# mehhhh.net
KiCad netlist of a schematic drawn in EAGLE
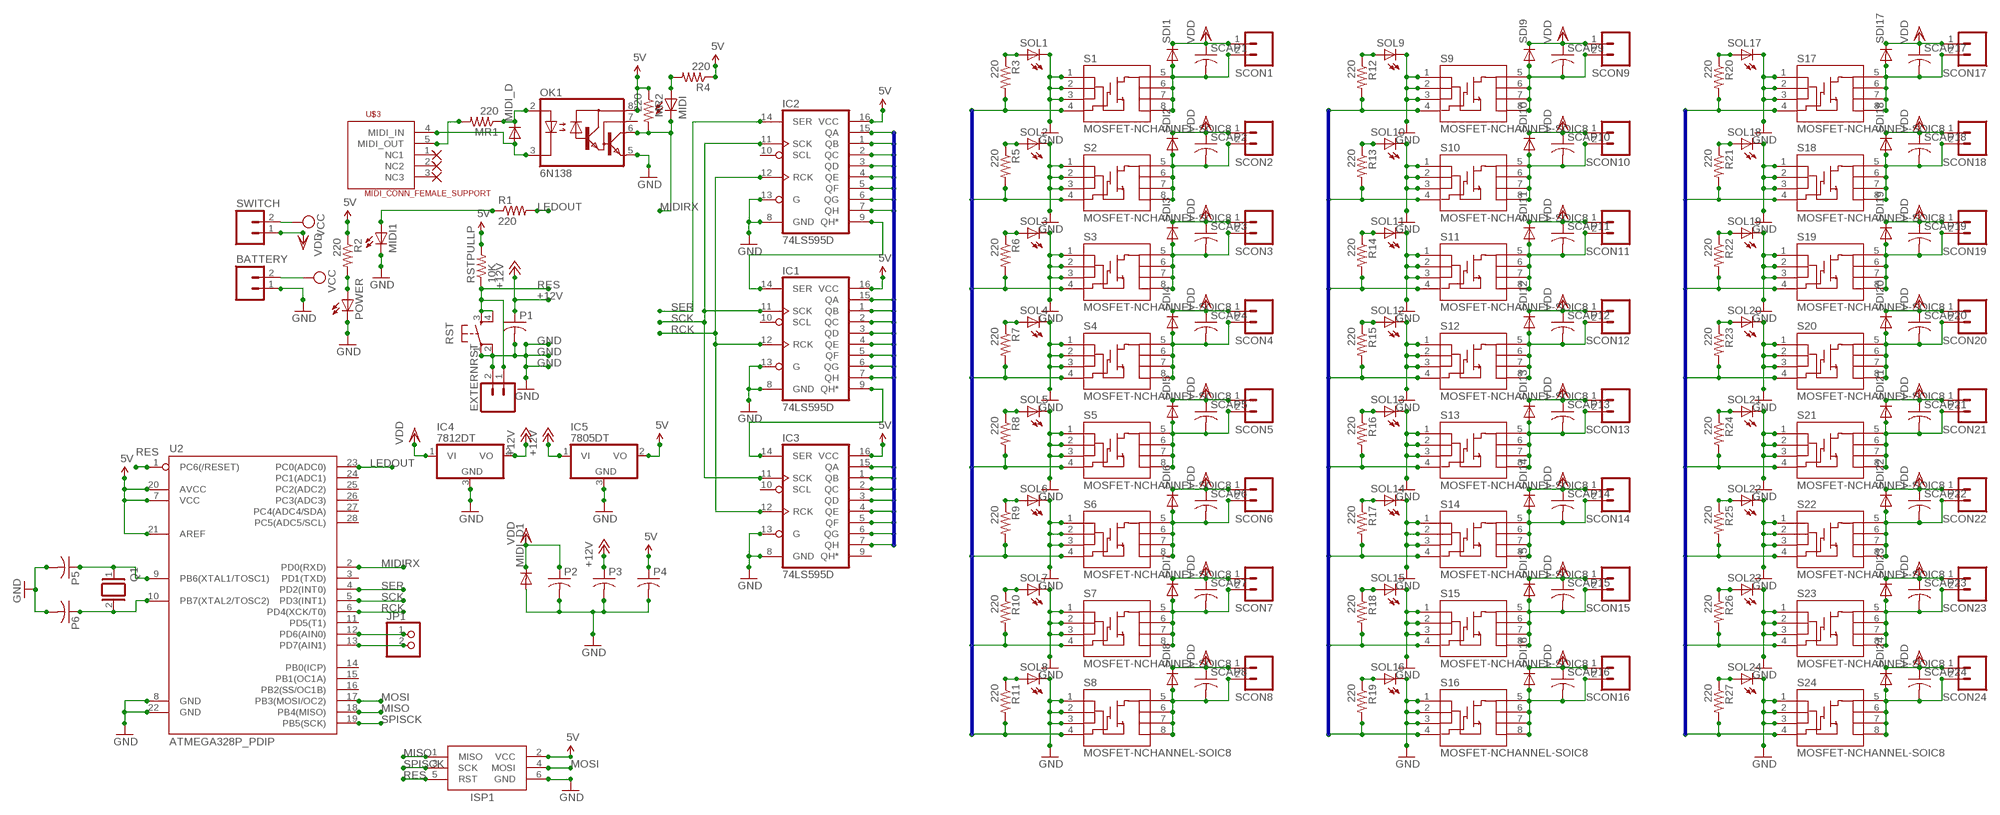
[diagram p0: schematic, sheet 1]

(export (version "E")
  (design (tool "Eeschema 10.0.6"))
  (components
    (comp (ref "BATTERY")
      (value "M023.5MM")
      (footprint "eagle-import:SCREWTERMINAL-3.5MM-2")
      (libsource (lib "eagle-import") (part "M023.5MM"))
    )
    (comp (ref "EXTERNRST")
      (value "M023.5MM")
      (footprint "eagle-import:SCREWTERMINAL-3.5MM-2")
      (libsource (lib "eagle-import") (part "M023.5MM"))
    )
    (comp (ref "IC1")
      (value "74LS595D")
      (footprint "eagle-import:SO16")
      (libsource (lib "eagle-import") (part "74595DLS"))
    )
    (comp (ref "IC2")
      (value "74LS595D")
      (footprint "eagle-import:SO16")
      (libsource (lib "eagle-import") (part "74595DLS"))
    )
    (comp (ref "IC3")
      (value "74LS595D")
      (footprint "eagle-import:SO16")
      (libsource (lib "eagle-import") (part "74595DLS"))
    )
    (comp (ref "IC4")
      (value "7812DT")
      (footprint "eagle-import:TO252")
      (libsource (lib "eagle-import") (part "78DT12"))
    )
    (comp (ref "IC5")
      (value "7805DT")
      (footprint "eagle-import:TO252")
      (libsource (lib "eagle-import") (part "78DT05"))
    )
    (comp (ref "ISP1")
      (value "AVRISP-6")
      (footprint "eagle-import:AVRISP")
      (libsource (lib "eagle-import") (part "AVRISP-6"))
    )
    (comp (ref "JP1")
      (value "PINHD-1X2")
      (footprint "eagle-import:1X02")
      (libsource (lib "eagle-import") (part "PINHD-1X2"))
    )
    (comp (ref "MIDI")
      (value "LEDCHIPLED_1206")
      (footprint "eagle-import:CHIPLED_1206")
      (libsource (lib "eagle-import") (part "LEDCHIPLED_1206"))
    )
    (comp (ref "MIDI1")
      (value "LEDCHIPLED_1206")
      (footprint "eagle-import:CHIPLED_1206")
      (libsource (lib "eagle-import") (part "LEDCHIPLED_1206"))
    )
    (comp (ref "MIDI_D")
      (value "DIODESMA-ALT")
      (footprint "eagle-import:SMA-DIODE_ALT")
      (libsource (lib "eagle-import") (part "DIODESMA-ALT"))
    )
    (comp (ref "MIDI_D1")
      (value "DIODESMA-ALT")
      (footprint "eagle-import:SMA-DIODE_ALT")
      (libsource (lib "eagle-import") (part "DIODESMA-ALT"))
    )
    (comp (ref "MR1")
      (value "220")
      (footprint "eagle-import:1206")
      (libsource (lib "eagle-import") (part "RESISTOR1206"))
    )
    (comp (ref "MR2")
      (value "220")
      (footprint "eagle-import:1206")
      (libsource (lib "eagle-import") (part "RESISTOR1206"))
    )
    (comp (ref "OK1")
      (value "6N138")
      (footprint "eagle-import:DIL08")
      (libsource (lib "eagle-import") (part "6N138"))
    )
    (comp (ref "P1")
      (value "C-USC1206")
      (footprint "eagle-import:C1206")
      (libsource (lib "eagle-import") (part "C-USC1206"))
    )
    (comp (ref "P2")
      (value "C-USC1206")
      (footprint "eagle-import:C1206")
      (libsource (lib "eagle-import") (part "C-USC1206"))
    )
    (comp (ref "P3")
      (value "C-USC1206")
      (footprint "eagle-import:C1206")
      (libsource (lib "eagle-import") (part "C-USC1206"))
    )
    (comp (ref "P4")
      (value "C-USC1206")
      (footprint "eagle-import:C1206")
      (libsource (lib "eagle-import") (part "C-USC1206"))
    )
    (comp (ref "P5")
      (value "C-USC1206")
      (footprint "eagle-import:C1206")
      (libsource (lib "eagle-import") (part "C-USC1206"))
    )
    (comp (ref "P6")
      (value "C-USC1206")
      (footprint "eagle-import:C1206")
      (libsource (lib "eagle-import") (part "C-USC1206"))
    )
    (comp (ref "POWER")
      (value "LEDCHIPLED_1206")
      (footprint "eagle-import:CHIPLED_1206")
      (libsource (lib "eagle-import") (part "LEDCHIPLED_1206"))
    )
    (comp (ref "Q1")
      (value "XTAL/S")
      (footprint "eagle-import:QS")
      (libsource (lib "eagle-import") (part "XTAL/S"))
    )
    (comp (ref "R1")
      (value "220")
      (footprint "eagle-import:1206")
      (libsource (lib "eagle-import") (part "RESISTOR1206"))
    )
    (comp (ref "R2")
      (value "220")
      (footprint "eagle-import:1206")
      (libsource (lib "eagle-import") (part "RESISTOR1206"))
    )
    (comp (ref "R3")
      (value "220")
      (footprint "eagle-import:1206")
      (libsource (lib "eagle-import") (part "RESISTOR1206"))
    )
    (comp (ref "R4")
      (value "220")
      (footprint "eagle-import:1206")
      (libsource (lib "eagle-import") (part "RESISTOR1206"))
    )
    (comp (ref "R5")
      (value "220")
      (footprint "eagle-import:1206")
      (libsource (lib "eagle-import") (part "RESISTOR1206"))
    )
    (comp (ref "R6")
      (value "220")
      (footprint "eagle-import:1206")
      (libsource (lib "eagle-import") (part "RESISTOR1206"))
    )
    (comp (ref "R7")
      (value "220")
      (footprint "eagle-import:1206")
      (libsource (lib "eagle-import") (part "RESISTOR1206"))
    )
    (comp (ref "R8")
      (value "220")
      (footprint "eagle-import:1206")
      (libsource (lib "eagle-import") (part "RESISTOR1206"))
    )
    (comp (ref "R9")
      (value "220")
      (footprint "eagle-import:1206")
      (libsource (lib "eagle-import") (part "RESISTOR1206"))
    )
    (comp (ref "R10")
      (value "220")
      (footprint "eagle-import:1206")
      (libsource (lib "eagle-import") (part "RESISTOR1206"))
    )
    (comp (ref "R11")
      (value "220")
      (footprint "eagle-import:1206")
      (libsource (lib "eagle-import") (part "RESISTOR1206"))
    )
    (comp (ref "R12")
      (value "220")
      (footprint "eagle-import:1206")
      (libsource (lib "eagle-import") (part "RESISTOR1206"))
    )
    (comp (ref "R13")
      (value "220")
      (footprint "eagle-import:1206")
      (libsource (lib "eagle-import") (part "RESISTOR1206"))
    )
    (comp (ref "R14")
      (value "220")
      (footprint "eagle-import:1206")
      (libsource (lib "eagle-import") (part "RESISTOR1206"))
    )
    (comp (ref "R15")
      (value "220")
      (footprint "eagle-import:1206")
      (libsource (lib "eagle-import") (part "RESISTOR1206"))
    )
    (comp (ref "R16")
      (value "220")
      (footprint "eagle-import:1206")
      (libsource (lib "eagle-import") (part "RESISTOR1206"))
    )
    (comp (ref "R17")
      (value "220")
      (footprint "eagle-import:1206")
      (libsource (lib "eagle-import") (part "RESISTOR1206"))
    )
    (comp (ref "R18")
      (value "220")
      (footprint "eagle-import:1206")
      (libsource (lib "eagle-import") (part "RESISTOR1206"))
    )
    (comp (ref "R19")
      (value "220")
      (footprint "eagle-import:1206")
      (libsource (lib "eagle-import") (part "RESISTOR1206"))
    )
    (comp (ref "R20")
      (value "220")
      (footprint "eagle-import:1206")
      (libsource (lib "eagle-import") (part "RESISTOR1206"))
    )
    (comp (ref "R21")
      (value "220")
      (footprint "eagle-import:1206")
      (libsource (lib "eagle-import") (part "RESISTOR1206"))
    )
    (comp (ref "R22")
      (value "220")
      (footprint "eagle-import:1206")
      (libsource (lib "eagle-import") (part "RESISTOR1206"))
    )
    (comp (ref "R23")
      (value "220")
      (footprint "eagle-import:1206")
      (libsource (lib "eagle-import") (part "RESISTOR1206"))
    )
    (comp (ref "R24")
      (value "220")
      (footprint "eagle-import:1206")
      (libsource (lib "eagle-import") (part "RESISTOR1206"))
    )
    (comp (ref "R25")
      (value "220")
      (footprint "eagle-import:1206")
      (libsource (lib "eagle-import") (part "RESISTOR1206"))
    )
    (comp (ref "R26")
      (value "220")
      (footprint "eagle-import:1206")
      (libsource (lib "eagle-import") (part "RESISTOR1206"))
    )
    (comp (ref "R27")
      (value "220")
      (footprint "eagle-import:1206")
      (libsource (lib "eagle-import") (part "RESISTOR1206"))
    )
    (comp (ref "RST")
      (value "TAC_SWITCHPTH")
      (footprint "eagle-import:TACTILE-PTH")
      (libsource (lib "eagle-import") (part "TAC_SWITCHPTH"))
    )
    (comp (ref "RSTPULLP")
      (value "10K")
      (footprint "eagle-import:1206")
      (libsource (lib "eagle-import") (part "RESISTOR1206"))
    )
    (comp (ref "S1")
      (value "MOSFET-NCHANNEL-SOIC8")
      (footprint "eagle-import:SO08")
      (libsource (lib "eagle-import") (part "MOSFET-NCHANNEL-SOIC8"))
    )
    (comp (ref "S2")
      (value "MOSFET-NCHANNEL-SOIC8")
      (footprint "eagle-import:SO08")
      (libsource (lib "eagle-import") (part "MOSFET-NCHANNEL-SOIC8"))
    )
    (comp (ref "S3")
      (value "MOSFET-NCHANNEL-SOIC8")
      (footprint "eagle-import:SO08")
      (libsource (lib "eagle-import") (part "MOSFET-NCHANNEL-SOIC8"))
    )
    (comp (ref "S4")
      (value "MOSFET-NCHANNEL-SOIC8")
      (footprint "eagle-import:SO08")
      (libsource (lib "eagle-import") (part "MOSFET-NCHANNEL-SOIC8"))
    )
    (comp (ref "S5")
      (value "MOSFET-NCHANNEL-SOIC8")
      (footprint "eagle-import:SO08")
      (libsource (lib "eagle-import") (part "MOSFET-NCHANNEL-SOIC8"))
    )
    (comp (ref "S6")
      (value "MOSFET-NCHANNEL-SOIC8")
      (footprint "eagle-import:SO08")
      (libsource (lib "eagle-import") (part "MOSFET-NCHANNEL-SOIC8"))
    )
    (comp (ref "S7")
      (value "MOSFET-NCHANNEL-SOIC8")
      (footprint "eagle-import:SO08")
      (libsource (lib "eagle-import") (part "MOSFET-NCHANNEL-SOIC8"))
    )
    (comp (ref "S8")
      (value "MOSFET-NCHANNEL-SOIC8")
      (footprint "eagle-import:SO08")
      (libsource (lib "eagle-import") (part "MOSFET-NCHANNEL-SOIC8"))
    )
    (comp (ref "S9")
      (value "MOSFET-NCHANNEL-SOIC8")
      (footprint "eagle-import:SO08")
      (libsource (lib "eagle-import") (part "MOSFET-NCHANNEL-SOIC8"))
    )
    (comp (ref "S10")
      (value "MOSFET-NCHANNEL-SOIC8")
      (footprint "eagle-import:SO08")
      (libsource (lib "eagle-import") (part "MOSFET-NCHANNEL-SOIC8"))
    )
    (comp (ref "S11")
      (value "MOSFET-NCHANNEL-SOIC8")
      (footprint "eagle-import:SO08")
      (libsource (lib "eagle-import") (part "MOSFET-NCHANNEL-SOIC8"))
    )
    (comp (ref "S12")
      (value "MOSFET-NCHANNEL-SOIC8")
      (footprint "eagle-import:SO08")
      (libsource (lib "eagle-import") (part "MOSFET-NCHANNEL-SOIC8"))
    )
    (comp (ref "S13")
      (value "MOSFET-NCHANNEL-SOIC8")
      (footprint "eagle-import:SO08")
      (libsource (lib "eagle-import") (part "MOSFET-NCHANNEL-SOIC8"))
    )
    (comp (ref "S14")
      (value "MOSFET-NCHANNEL-SOIC8")
      (footprint "eagle-import:SO08")
      (libsource (lib "eagle-import") (part "MOSFET-NCHANNEL-SOIC8"))
    )
    (comp (ref "S15")
      (value "MOSFET-NCHANNEL-SOIC8")
      (footprint "eagle-import:SO08")
      (libsource (lib "eagle-import") (part "MOSFET-NCHANNEL-SOIC8"))
    )
    (comp (ref "S16")
      (value "MOSFET-NCHANNEL-SOIC8")
      (footprint "eagle-import:SO08")
      (libsource (lib "eagle-import") (part "MOSFET-NCHANNEL-SOIC8"))
    )
    (comp (ref "S17")
      (value "MOSFET-NCHANNEL-SOIC8")
      (footprint "eagle-import:SO08")
      (libsource (lib "eagle-import") (part "MOSFET-NCHANNEL-SOIC8"))
    )
    (comp (ref "S18")
      (value "MOSFET-NCHANNEL-SOIC8")
      (footprint "eagle-import:SO08")
      (libsource (lib "eagle-import") (part "MOSFET-NCHANNEL-SOIC8"))
    )
    (comp (ref "S19")
      (value "MOSFET-NCHANNEL-SOIC8")
      (footprint "eagle-import:SO08")
      (libsource (lib "eagle-import") (part "MOSFET-NCHANNEL-SOIC8"))
    )
    (comp (ref "S20")
      (value "MOSFET-NCHANNEL-SOIC8")
      (footprint "eagle-import:SO08")
      (libsource (lib "eagle-import") (part "MOSFET-NCHANNEL-SOIC8"))
    )
    (comp (ref "S21")
      (value "MOSFET-NCHANNEL-SOIC8")
      (footprint "eagle-import:SO08")
      (libsource (lib "eagle-import") (part "MOSFET-NCHANNEL-SOIC8"))
    )
    (comp (ref "S22")
      (value "MOSFET-NCHANNEL-SOIC8")
      (footprint "eagle-import:SO08")
      (libsource (lib "eagle-import") (part "MOSFET-NCHANNEL-SOIC8"))
    )
    (comp (ref "S23")
      (value "MOSFET-NCHANNEL-SOIC8")
      (footprint "eagle-import:SO08")
      (libsource (lib "eagle-import") (part "MOSFET-NCHANNEL-SOIC8"))
    )
    (comp (ref "S24")
      (value "MOSFET-NCHANNEL-SOIC8")
      (footprint "eagle-import:SO08")
      (libsource (lib "eagle-import") (part "MOSFET-NCHANNEL-SOIC8"))
    )
    (comp (ref "SCAP1")
      (value "C-USC1206")
      (footprint "eagle-import:C1206")
      (libsource (lib "eagle-import") (part "C-USC1206"))
    )
    (comp (ref "SCAP2")
      (value "C-USC1206")
      (footprint "eagle-import:C1206")
      (libsource (lib "eagle-import") (part "C-USC1206"))
    )
    (comp (ref "SCAP3")
      (value "C-USC1206")
      (footprint "eagle-import:C1206")
      (libsource (lib "eagle-import") (part "C-USC1206"))
    )
    (comp (ref "SCAP4")
      (value "C-USC1206")
      (footprint "eagle-import:C1206")
      (libsource (lib "eagle-import") (part "C-USC1206"))
    )
    (comp (ref "SCAP5")
      (value "C-USC1206")
      (footprint "eagle-import:C1206")
      (libsource (lib "eagle-import") (part "C-USC1206"))
    )
    (comp (ref "SCAP6")
      (value "C-USC1206")
      (footprint "eagle-import:C1206")
      (libsource (lib "eagle-import") (part "C-USC1206"))
    )
    (comp (ref "SCAP7")
      (value "C-USC1206")
      (footprint "eagle-import:C1206")
      (libsource (lib "eagle-import") (part "C-USC1206"))
    )
    (comp (ref "SCAP8")
      (value "C-USC1206")
      (footprint "eagle-import:C1206")
      (libsource (lib "eagle-import") (part "C-USC1206"))
    )
    (comp (ref "SCAP9")
      (value "C-USC1206")
      (footprint "eagle-import:C1206")
      (libsource (lib "eagle-import") (part "C-USC1206"))
    )
    (comp (ref "SCAP10")
      (value "C-USC1206")
      (footprint "eagle-import:C1206")
      (libsource (lib "eagle-import") (part "C-USC1206"))
    )
    (comp (ref "SCAP11")
      (value "C-USC1206")
      (footprint "eagle-import:C1206")
      (libsource (lib "eagle-import") (part "C-USC1206"))
    )
    (comp (ref "SCAP12")
      (value "C-USC1206")
      (footprint "eagle-import:C1206")
      (libsource (lib "eagle-import") (part "C-USC1206"))
    )
    (comp (ref "SCAP13")
      (value "C-USC1206")
      (footprint "eagle-import:C1206")
      (libsource (lib "eagle-import") (part "C-USC1206"))
    )
    (comp (ref "SCAP14")
      (value "C-USC1206")
      (footprint "eagle-import:C1206")
      (libsource (lib "eagle-import") (part "C-USC1206"))
    )
    (comp (ref "SCAP15")
      (value "C-USC1206")
      (footprint "eagle-import:C1206")
      (libsource (lib "eagle-import") (part "C-USC1206"))
    )
    (comp (ref "SCAP16")
      (value "C-USC1206")
      (footprint "eagle-import:C1206")
      (libsource (lib "eagle-import") (part "C-USC1206"))
    )
    (comp (ref "SCAP17")
      (value "C-USC1206")
      (footprint "eagle-import:C1206")
      (libsource (lib "eagle-import") (part "C-USC1206"))
    )
    (comp (ref "SCAP18")
      (value "C-USC1206")
      (footprint "eagle-import:C1206")
      (libsource (lib "eagle-import") (part "C-USC1206"))
    )
    (comp (ref "SCAP19")
      (value "C-USC1206")
      (footprint "eagle-import:C1206")
      (libsource (lib "eagle-import") (part "C-USC1206"))
    )
    (comp (ref "SCAP20")
      (value "C-USC1206")
      (footprint "eagle-import:C1206")
      (libsource (lib "eagle-import") (part "C-USC1206"))
    )
    (comp (ref "SCAP21")
      (value "C-USC1206")
      (footprint "eagle-import:C1206")
      (libsource (lib "eagle-import") (part "C-USC1206"))
    )
    (comp (ref "SCAP22")
      (value "C-USC1206")
      (footprint "eagle-import:C1206")
      (libsource (lib "eagle-import") (part "C-USC1206"))
    )
    (comp (ref "SCAP23")
      (value "C-USC1206")
      (footprint "eagle-import:C1206")
      (libsource (lib "eagle-import") (part "C-USC1206"))
    )
    (comp (ref "SCAP24")
      (value "C-USC1206")
      (footprint "eagle-import:C1206")
      (libsource (lib "eagle-import") (part "C-USC1206"))
    )
    (comp (ref "SCON1")
      (value "M023.5MM")
      (footprint "eagle-import:SCREWTERMINAL-3.5MM-2")
      (libsource (lib "eagle-import") (part "M023.5MM"))
    )
    (comp (ref "SCON2")
      (value "M023.5MM")
      (footprint "eagle-import:SCREWTERMINAL-3.5MM-2")
      (libsource (lib "eagle-import") (part "M023.5MM"))
    )
    (comp (ref "SCON3")
      (value "M023.5MM")
      (footprint "eagle-import:SCREWTERMINAL-3.5MM-2")
      (libsource (lib "eagle-import") (part "M023.5MM"))
    )
    (comp (ref "SCON4")
      (value "M023.5MM")
      (footprint "eagle-import:SCREWTERMINAL-3.5MM-2")
      (libsource (lib "eagle-import") (part "M023.5MM"))
    )
    (comp (ref "SCON5")
      (value "M023.5MM")
      (footprint "eagle-import:SCREWTERMINAL-3.5MM-2")
      (libsource (lib "eagle-import") (part "M023.5MM"))
    )
    (comp (ref "SCON6")
      (value "M023.5MM")
      (footprint "eagle-import:SCREWTERMINAL-3.5MM-2")
      (libsource (lib "eagle-import") (part "M023.5MM"))
    )
    (comp (ref "SCON7")
      (value "M023.5MM")
      (footprint "eagle-import:SCREWTERMINAL-3.5MM-2")
      (libsource (lib "eagle-import") (part "M023.5MM"))
    )
    (comp (ref "SCON8")
      (value "M023.5MM")
      (footprint "eagle-import:SCREWTERMINAL-3.5MM-2")
      (libsource (lib "eagle-import") (part "M023.5MM"))
    )
    (comp (ref "SCON9")
      (value "M023.5MM")
      (footprint "eagle-import:SCREWTERMINAL-3.5MM-2")
      (libsource (lib "eagle-import") (part "M023.5MM"))
    )
    (comp (ref "SCON10")
      (value "M023.5MM")
      (footprint "eagle-import:SCREWTERMINAL-3.5MM-2")
      (libsource (lib "eagle-import") (part "M023.5MM"))
    )
    (comp (ref "SCON11")
      (value "M023.5MM")
      (footprint "eagle-import:SCREWTERMINAL-3.5MM-2")
      (libsource (lib "eagle-import") (part "M023.5MM"))
    )
    (comp (ref "SCON12")
      (value "M023.5MM")
      (footprint "eagle-import:SCREWTERMINAL-3.5MM-2")
      (libsource (lib "eagle-import") (part "M023.5MM"))
    )
    (comp (ref "SCON13")
      (value "M023.5MM")
      (footprint "eagle-import:SCREWTERMINAL-3.5MM-2")
      (libsource (lib "eagle-import") (part "M023.5MM"))
    )
    (comp (ref "SCON14")
      (value "M023.5MM")
      (footprint "eagle-import:SCREWTERMINAL-3.5MM-2")
      (libsource (lib "eagle-import") (part "M023.5MM"))
    )
    (comp (ref "SCON15")
      (value "M023.5MM")
      (footprint "eagle-import:SCREWTERMINAL-3.5MM-2")
      (libsource (lib "eagle-import") (part "M023.5MM"))
    )
    (comp (ref "SCON16")
      (value "M023.5MM")
      (footprint "eagle-import:SCREWTERMINAL-3.5MM-2")
      (libsource (lib "eagle-import") (part "M023.5MM"))
    )
    (comp (ref "SCON17")
      (value "M023.5MM")
      (footprint "eagle-import:SCREWTERMINAL-3.5MM-2")
      (libsource (lib "eagle-import") (part "M023.5MM"))
    )
    (comp (ref "SCON18")
      (value "M023.5MM")
      (footprint "eagle-import:SCREWTERMINAL-3.5MM-2")
      (libsource (lib "eagle-import") (part "M023.5MM"))
    )
    (comp (ref "SCON19")
      (value "M023.5MM")
      (footprint "eagle-import:SCREWTERMINAL-3.5MM-2")
      (libsource (lib "eagle-import") (part "M023.5MM"))
    )
    (comp (ref "SCON20")
      (value "M023.5MM")
      (footprint "eagle-import:SCREWTERMINAL-3.5MM-2")
      (libsource (lib "eagle-import") (part "M023.5MM"))
    )
    (comp (ref "SCON21")
      (value "M023.5MM")
      (footprint "eagle-import:SCREWTERMINAL-3.5MM-2")
      (libsource (lib "eagle-import") (part "M023.5MM"))
    )
    (comp (ref "SCON22")
      (value "M023.5MM")
      (footprint "eagle-import:SCREWTERMINAL-3.5MM-2")
      (libsource (lib "eagle-import") (part "M023.5MM"))
    )
    (comp (ref "SCON23")
      (value "M023.5MM")
      (footprint "eagle-import:SCREWTERMINAL-3.5MM-2")
      (libsource (lib "eagle-import") (part "M023.5MM"))
    )
    (comp (ref "SCON24")
      (value "M023.5MM")
      (footprint "eagle-import:SCREWTERMINAL-3.5MM-2")
      (libsource (lib "eagle-import") (part "M023.5MM"))
    )
    (comp (ref "SDI1")
      (value "DIODESMA-ALT")
      (footprint "eagle-import:SMA-DIODE_ALT")
      (libsource (lib "eagle-import") (part "DIODESMA-ALT"))
    )
    (comp (ref "SDI2")
      (value "DIODESMA-ALT")
      (footprint "eagle-import:SMA-DIODE_ALT")
      (libsource (lib "eagle-import") (part "DIODESMA-ALT"))
    )
    (comp (ref "SDI3")
      (value "DIODESMA-ALT")
      (footprint "eagle-import:SMA-DIODE_ALT")
      (libsource (lib "eagle-import") (part "DIODESMA-ALT"))
    )
    (comp (ref "SDI4")
      (value "DIODESMA-ALT")
      (footprint "eagle-import:SMA-DIODE_ALT")
      (libsource (lib "eagle-import") (part "DIODESMA-ALT"))
    )
    (comp (ref "SDI5")
      (value "DIODESMA-ALT")
      (footprint "eagle-import:SMA-DIODE_ALT")
      (libsource (lib "eagle-import") (part "DIODESMA-ALT"))
    )
    (comp (ref "SDI6")
      (value "DIODESMA-ALT")
      (footprint "eagle-import:SMA-DIODE_ALT")
      (libsource (lib "eagle-import") (part "DIODESMA-ALT"))
    )
    (comp (ref "SDI7")
      (value "DIODESMA-ALT")
      (footprint "eagle-import:SMA-DIODE_ALT")
      (libsource (lib "eagle-import") (part "DIODESMA-ALT"))
    )
    (comp (ref "SDI8")
      (value "DIODESMA-ALT")
      (footprint "eagle-import:SMA-DIODE_ALT")
      (libsource (lib "eagle-import") (part "DIODESMA-ALT"))
    )
    (comp (ref "SDI9")
      (value "DIODESMA-ALT")
      (footprint "eagle-import:SMA-DIODE_ALT")
      (libsource (lib "eagle-import") (part "DIODESMA-ALT"))
    )
    (comp (ref "SDI10")
      (value "DIODESMA-ALT")
      (footprint "eagle-import:SMA-DIODE_ALT")
      (libsource (lib "eagle-import") (part "DIODESMA-ALT"))
    )
    (comp (ref "SDI11")
      (value "DIODESMA-ALT")
      (footprint "eagle-import:SMA-DIODE_ALT")
      (libsource (lib "eagle-import") (part "DIODESMA-ALT"))
    )
    (comp (ref "SDI12")
      (value "DIODESMA-ALT")
      (footprint "eagle-import:SMA-DIODE_ALT")
      (libsource (lib "eagle-import") (part "DIODESMA-ALT"))
    )
    (comp (ref "SDI13")
      (value "DIODESMA-ALT")
      (footprint "eagle-import:SMA-DIODE_ALT")
      (libsource (lib "eagle-import") (part "DIODESMA-ALT"))
    )
    (comp (ref "SDI14")
      (value "DIODESMA-ALT")
      (footprint "eagle-import:SMA-DIODE_ALT")
      (libsource (lib "eagle-import") (part "DIODESMA-ALT"))
    )
    (comp (ref "SDI15")
      (value "DIODESMA-ALT")
      (footprint "eagle-import:SMA-DIODE_ALT")
      (libsource (lib "eagle-import") (part "DIODESMA-ALT"))
    )
    (comp (ref "SDI16")
      (value "DIODESMA-ALT")
      (footprint "eagle-import:SMA-DIODE_ALT")
      (libsource (lib "eagle-import") (part "DIODESMA-ALT"))
    )
    (comp (ref "SDI17")
      (value "DIODESMA-ALT")
      (footprint "eagle-import:SMA-DIODE_ALT")
      (libsource (lib "eagle-import") (part "DIODESMA-ALT"))
    )
    (comp (ref "SDI18")
      (value "DIODESMA-ALT")
      (footprint "eagle-import:SMA-DIODE_ALT")
      (libsource (lib "eagle-import") (part "DIODESMA-ALT"))
    )
    (comp (ref "SDI19")
      (value "DIODESMA-ALT")
      (footprint "eagle-import:SMA-DIODE_ALT")
      (libsource (lib "eagle-import") (part "DIODESMA-ALT"))
    )
    (comp (ref "SDI20")
      (value "DIODESMA-ALT")
      (footprint "eagle-import:SMA-DIODE_ALT")
      (libsource (lib "eagle-import") (part "DIODESMA-ALT"))
    )
    (comp (ref "SDI21")
      (value "DIODESMA-ALT")
      (footprint "eagle-import:SMA-DIODE_ALT")
      (libsource (lib "eagle-import") (part "DIODESMA-ALT"))
    )
    (comp (ref "SDI22")
      (value "DIODESMA-ALT")
      (footprint "eagle-import:SMA-DIODE_ALT")
      (libsource (lib "eagle-import") (part "DIODESMA-ALT"))
    )
    (comp (ref "SDI23")
      (value "DIODESMA-ALT")
      (footprint "eagle-import:SMA-DIODE_ALT")
      (libsource (lib "eagle-import") (part "DIODESMA-ALT"))
    )
    (comp (ref "SDI24")
      (value "DIODESMA-ALT")
      (footprint "eagle-import:SMA-DIODE_ALT")
      (libsource (lib "eagle-import") (part "DIODESMA-ALT"))
    )
    (comp (ref "SOL1")
      (value "LEDCHIPLED_1206")
      (footprint "eagle-import:CHIPLED_1206")
      (libsource (lib "eagle-import") (part "LEDCHIPLED_1206"))
    )
    (comp (ref "SOL2")
      (value "LEDCHIPLED_1206")
      (footprint "eagle-import:CHIPLED_1206")
      (libsource (lib "eagle-import") (part "LEDCHIPLED_1206"))
    )
    (comp (ref "SOL3")
      (value "LEDCHIPLED_1206")
      (footprint "eagle-import:CHIPLED_1206")
      (libsource (lib "eagle-import") (part "LEDCHIPLED_1206"))
    )
    (comp (ref "SOL4")
      (value "LEDCHIPLED_1206")
      (footprint "eagle-import:CHIPLED_1206")
      (libsource (lib "eagle-import") (part "LEDCHIPLED_1206"))
    )
    (comp (ref "SOL5")
      (value "LEDCHIPLED_1206")
      (footprint "eagle-import:CHIPLED_1206")
      (libsource (lib "eagle-import") (part "LEDCHIPLED_1206"))
    )
    (comp (ref "SOL6")
      (value "LEDCHIPLED_1206")
      (footprint "eagle-import:CHIPLED_1206")
      (libsource (lib "eagle-import") (part "LEDCHIPLED_1206"))
    )
    (comp (ref "SOL7")
      (value "LEDCHIPLED_1206")
      (footprint "eagle-import:CHIPLED_1206")
      (libsource (lib "eagle-import") (part "LEDCHIPLED_1206"))
    )
    (comp (ref "SOL8")
      (value "LEDCHIPLED_1206")
      (footprint "eagle-import:CHIPLED_1206")
      (libsource (lib "eagle-import") (part "LEDCHIPLED_1206"))
    )
    (comp (ref "SOL9")
      (value "LEDCHIPLED_1206")
      (footprint "eagle-import:CHIPLED_1206")
      (libsource (lib "eagle-import") (part "LEDCHIPLED_1206"))
    )
    (comp (ref "SOL10")
      (value "LEDCHIPLED_1206")
      (footprint "eagle-import:CHIPLED_1206")
      (libsource (lib "eagle-import") (part "LEDCHIPLED_1206"))
    )
    (comp (ref "SOL11")
      (value "LEDCHIPLED_1206")
      (footprint "eagle-import:CHIPLED_1206")
      (libsource (lib "eagle-import") (part "LEDCHIPLED_1206"))
    )
    (comp (ref "SOL12")
      (value "LEDCHIPLED_1206")
      (footprint "eagle-import:CHIPLED_1206")
      (libsource (lib "eagle-import") (part "LEDCHIPLED_1206"))
    )
    (comp (ref "SOL13")
      (value "LEDCHIPLED_1206")
      (footprint "eagle-import:CHIPLED_1206")
      (libsource (lib "eagle-import") (part "LEDCHIPLED_1206"))
    )
    (comp (ref "SOL14")
      (value "LEDCHIPLED_1206")
      (footprint "eagle-import:CHIPLED_1206")
      (libsource (lib "eagle-import") (part "LEDCHIPLED_1206"))
    )
    (comp (ref "SOL15")
      (value "LEDCHIPLED_1206")
      (footprint "eagle-import:CHIPLED_1206")
      (libsource (lib "eagle-import") (part "LEDCHIPLED_1206"))
    )
    (comp (ref "SOL16")
      (value "LEDCHIPLED_1206")
      (footprint "eagle-import:CHIPLED_1206")
      (libsource (lib "eagle-import") (part "LEDCHIPLED_1206"))
    )
    (comp (ref "SOL17")
      (value "LEDCHIPLED_1206")
      (footprint "eagle-import:CHIPLED_1206")
      (libsource (lib "eagle-import") (part "LEDCHIPLED_1206"))
    )
    (comp (ref "SOL18")
      (value "LEDCHIPLED_1206")
      (footprint "eagle-import:CHIPLED_1206")
      (libsource (lib "eagle-import") (part "LEDCHIPLED_1206"))
    )
    (comp (ref "SOL19")
      (value "LEDCHIPLED_1206")
      (footprint "eagle-import:CHIPLED_1206")
      (libsource (lib "eagle-import") (part "LEDCHIPLED_1206"))
    )
    (comp (ref "SOL20")
      (value "LEDCHIPLED_1206")
      (footprint "eagle-import:CHIPLED_1206")
      (libsource (lib "eagle-import") (part "LEDCHIPLED_1206"))
    )
    (comp (ref "SOL21")
      (value "LEDCHIPLED_1206")
      (footprint "eagle-import:CHIPLED_1206")
      (libsource (lib "eagle-import") (part "LEDCHIPLED_1206"))
    )
    (comp (ref "SOL22")
      (value "LEDCHIPLED_1206")
      (footprint "eagle-import:CHIPLED_1206")
      (libsource (lib "eagle-import") (part "LEDCHIPLED_1206"))
    )
    (comp (ref "SOL23")
      (value "LEDCHIPLED_1206")
      (footprint "eagle-import:CHIPLED_1206")
      (libsource (lib "eagle-import") (part "LEDCHIPLED_1206"))
    )
    (comp (ref "SOL24")
      (value "LEDCHIPLED_1206")
      (footprint "eagle-import:CHIPLED_1206")
      (libsource (lib "eagle-import") (part "LEDCHIPLED_1206"))
    )
    (comp (ref "SWITCH")
      (value "M023.5MM")
      (footprint "eagle-import:SCREWTERMINAL-3.5MM-2")
      (libsource (lib "eagle-import") (part "M023.5MM"))
    )
    (comp (ref "U$3")
      (value "MIDI_CONN_FEMALE_SUPPORT")
      (footprint "eagle-import:DIN_5_FEMALE_SUPPORT")
      (libsource (lib "eagle-import") (part "MIDI_CONN_FEMALE_SUPPORT"))
    )
    (comp (ref "U2")
      (value "ATMEGA328P_PDIP")
      (footprint "eagle-import:DIL28-3")
      (libsource (lib "eagle-import") (part "ATMEGA328P_PDIP"))
    )
  )
  (nets
    (net (code "1") (name "+12V") (class "Default")
      (node (ref "IC4") (pin "2") (pinfunction "VO_2") (pintype "passive"))
      (node (ref "IC5") (pin "1") (pinfunction "VI_1") (pintype "input"))
      (node (ref "P1") (pin "1") (pinfunction "1_1") (pintype "passive"))
      (node (ref "P3") (pin "1") (pinfunction "1_1") (pintype "passive"))
    )
    (net (code "2") (name "/LEDOUT") (class "Default")
      (node (ref "R1") (pin "2") (pinfunction "2_2") (pintype "passive"))
      (node (ref "U2") (pin "23") (pinfunction "PC0(ADC0)_23") (pintype "bidirectional"))
    )
    (net (code "3") (name "/MIDIRX") (class "Default")
      (node (ref "MIDI") (pin "C") (pinfunction "C_C") (pintype "passive"))
      (node (ref "MR2") (pin "2") (pinfunction "2_2") (pintype "passive"))
      (node (ref "OK1") (pin "6") (pinfunction "VO_6") (pintype "passive"))
      (node (ref "U2") (pin "2") (pinfunction "PD0(RXD)_2") (pintype "bidirectional"))
    )
    (net (code "4") (name "/MISO") (class "Default")
      (node (ref "ISP1") (pin "1") (pinfunction "MISO_1") (pintype "input"))
      (node (ref "U2") (pin "18") (pinfunction "PB4(MISO)_18") (pintype "bidirectional"))
    )
    (net (code "5") (name "/MOSI") (class "Default")
      (node (ref "ISP1") (pin "4") (pinfunction "MOSI_4") (pintype "output"))
      (node (ref "U2") (pin "17") (pinfunction "PB3(MOSI/OC2)_17") (pintype "bidirectional"))
    )
    (net (code "6") (name "/RCK") (class "Default")
      (node (ref "IC1") (pin "12") (pinfunction "RCK_12") (pintype "input"))
      (node (ref "IC2") (pin "12") (pinfunction "RCK_12") (pintype "input"))
      (node (ref "IC3") (pin "12") (pinfunction "RCK_12") (pintype "input"))
      (node (ref "U2") (pin "6") (pinfunction "PD4(XCK/T0)_6") (pintype "bidirectional"))
    )
    (net (code "7") (name "/RES") (class "Default")
      (node (ref "EXTERNRST") (pin "1") (pinfunction "1_1") (pintype "passive"))
      (node (ref "ISP1") (pin "5") (pinfunction "RST_5") (pintype "output"))
      (node (ref "RST") (pin "3") (pinfunction "3_3") (pintype "passive"))
      (node (ref "RST") (pin "4") (pinfunction "4_4") (pintype "passive"))
      (node (ref "RSTPULLP") (pin "1") (pinfunction "1_1") (pintype "passive"))
      (node (ref "U2") (pin "1") (pinfunction "PC6(/RESET)_1") (pintype "bidirectional"))
    )
    (net (code "8") (name "/SCK") (class "Default")
      (node (ref "IC1") (pin "11") (pinfunction "SCK_11") (pintype "input"))
      (node (ref "IC2") (pin "11") (pinfunction "SCK_11") (pintype "input"))
      (node (ref "IC3") (pin "11") (pinfunction "SCK_11") (pintype "input"))
      (node (ref "U2") (pin "5") (pinfunction "PD3(INT1)_5") (pintype "bidirectional"))
    )
    (net (code "9") (name "/SER") (class "Default")
      (node (ref "IC2") (pin "14") (pinfunction "SER_14") (pintype "input"))
      (node (ref "U2") (pin "4") (pinfunction "PD2(INT0)_4") (pintype "bidirectional"))
    )
    (net (code "10") (name "/SHIFTOUT0") (class "Default")
      (node (ref "IC2") (pin "15") (pinfunction "QA_15") (pintype "tri_state"))
      (node (ref "R3") (pin "2") (pinfunction "2_2") (pintype "passive"))
      (node (ref "S1") (pin "4") (pinfunction "G_4") (pintype "bidirectional"))
    )
    (net (code "11") (name "/SHIFTOUT1") (class "Default")
      (node (ref "IC2") (pin "1") (pinfunction "QB_1") (pintype "tri_state"))
      (node (ref "R5") (pin "2") (pinfunction "2_2") (pintype "passive"))
      (node (ref "S2") (pin "4") (pinfunction "G_4") (pintype "bidirectional"))
    )
    (net (code "12") (name "/SHIFTOUT2") (class "Default")
      (node (ref "IC2") (pin "2") (pinfunction "QC_2") (pintype "tri_state"))
      (node (ref "R6") (pin "2") (pinfunction "2_2") (pintype "passive"))
      (node (ref "S3") (pin "4") (pinfunction "G_4") (pintype "bidirectional"))
    )
    (net (code "13") (name "/SHIFTOUT3") (class "Default")
      (node (ref "IC2") (pin "3") (pinfunction "QD_3") (pintype "tri_state"))
      (node (ref "R7") (pin "2") (pinfunction "2_2") (pintype "passive"))
      (node (ref "S4") (pin "4") (pinfunction "G_4") (pintype "bidirectional"))
    )
    (net (code "14") (name "/SHIFTOUT4") (class "Default")
      (node (ref "IC2") (pin "4") (pinfunction "QE_4") (pintype "tri_state"))
      (node (ref "R8") (pin "2") (pinfunction "2_2") (pintype "passive"))
      (node (ref "S5") (pin "4") (pinfunction "G_4") (pintype "bidirectional"))
    )
    (net (code "15") (name "/SHIFTOUT5") (class "Default")
      (node (ref "IC2") (pin "5") (pinfunction "QF_5") (pintype "tri_state"))
      (node (ref "R9") (pin "2") (pinfunction "2_2") (pintype "passive"))
      (node (ref "S6") (pin "4") (pinfunction "G_4") (pintype "bidirectional"))
    )
    (net (code "16") (name "/SHIFTOUT6") (class "Default")
      (node (ref "IC2") (pin "6") (pinfunction "QG_6") (pintype "tri_state"))
      (node (ref "R10") (pin "2") (pinfunction "2_2") (pintype "passive"))
      (node (ref "S7") (pin "4") (pinfunction "G_4") (pintype "bidirectional"))
    )
    (net (code "17") (name "/SHIFTOUT7") (class "Default")
      (node (ref "IC2") (pin "7") (pinfunction "QH_7") (pintype "tri_state"))
      (node (ref "R11") (pin "2") (pinfunction "2_2") (pintype "passive"))
      (node (ref "S8") (pin "4") (pinfunction "G_4") (pintype "bidirectional"))
    )
    (net (code "18") (name "/SHIFTOUT8") (class "Default")
      (node (ref "IC1") (pin "15") (pinfunction "QA_15") (pintype "tri_state"))
      (node (ref "R19") (pin "2") (pinfunction "2_2") (pintype "passive"))
      (node (ref "S16") (pin "4") (pinfunction "G_4") (pintype "bidirectional"))
    )
    (net (code "19") (name "/SHIFTOUT9") (class "Default")
      (node (ref "IC1") (pin "1") (pinfunction "QB_1") (pintype "tri_state"))
      (node (ref "R18") (pin "2") (pinfunction "2_2") (pintype "passive"))
      (node (ref "S15") (pin "4") (pinfunction "G_4") (pintype "bidirectional"))
    )
    (net (code "20") (name "/SHIFTOUT10") (class "Default")
      (node (ref "IC1") (pin "2") (pinfunction "QC_2") (pintype "tri_state"))
      (node (ref "R17") (pin "2") (pinfunction "2_2") (pintype "passive"))
      (node (ref "S14") (pin "4") (pinfunction "G_4") (pintype "bidirectional"))
    )
    (net (code "21") (name "/SHIFTOUT11") (class "Default")
      (node (ref "IC1") (pin "3") (pinfunction "QD_3") (pintype "tri_state"))
      (node (ref "R16") (pin "2") (pinfunction "2_2") (pintype "passive"))
      (node (ref "S13") (pin "4") (pinfunction "G_4") (pintype "bidirectional"))
    )
    (net (code "22") (name "/SHIFTOUT12") (class "Default")
      (node (ref "IC1") (pin "4") (pinfunction "QE_4") (pintype "tri_state"))
      (node (ref "R15") (pin "2") (pinfunction "2_2") (pintype "passive"))
      (node (ref "S12") (pin "4") (pinfunction "G_4") (pintype "bidirectional"))
    )
    (net (code "23") (name "/SHIFTOUT13") (class "Default")
      (node (ref "IC1") (pin "5") (pinfunction "QF_5") (pintype "tri_state"))
      (node (ref "R14") (pin "2") (pinfunction "2_2") (pintype "passive"))
      (node (ref "S11") (pin "4") (pinfunction "G_4") (pintype "bidirectional"))
    )
    (net (code "24") (name "/SHIFTOUT14") (class "Default")
      (node (ref "IC1") (pin "6") (pinfunction "QG_6") (pintype "tri_state"))
      (node (ref "R13") (pin "2") (pinfunction "2_2") (pintype "passive"))
      (node (ref "S10") (pin "4") (pinfunction "G_4") (pintype "bidirectional"))
    )
    (net (code "25") (name "/SHIFTOUT15") (class "Default")
      (node (ref "IC1") (pin "7") (pinfunction "QH_7") (pintype "tri_state"))
      (node (ref "R12") (pin "2") (pinfunction "2_2") (pintype "passive"))
      (node (ref "S9") (pin "4") (pinfunction "G_4") (pintype "bidirectional"))
    )
    (net (code "26") (name "/SHIFTOUT16") (class "Default")
      (node (ref "IC3") (pin "15") (pinfunction "QA_15") (pintype "tri_state"))
      (node (ref "R20") (pin "2") (pinfunction "2_2") (pintype "passive"))
      (node (ref "S17") (pin "4") (pinfunction "G_4") (pintype "bidirectional"))
    )
    (net (code "27") (name "/SHIFTOUT17") (class "Default")
      (node (ref "IC3") (pin "1") (pinfunction "QB_1") (pintype "tri_state"))
      (node (ref "R21") (pin "2") (pinfunction "2_2") (pintype "passive"))
      (node (ref "S18") (pin "4") (pinfunction "G_4") (pintype "bidirectional"))
    )
    (net (code "28") (name "/SHIFTOUT18") (class "Default")
      (node (ref "IC3") (pin "2") (pinfunction "QC_2") (pintype "tri_state"))
      (node (ref "R22") (pin "2") (pinfunction "2_2") (pintype "passive"))
      (node (ref "S19") (pin "4") (pinfunction "G_4") (pintype "bidirectional"))
    )
    (net (code "29") (name "/SHIFTOUT19") (class "Default")
      (node (ref "IC3") (pin "3") (pinfunction "QD_3") (pintype "tri_state"))
      (node (ref "R23") (pin "2") (pinfunction "2_2") (pintype "passive"))
      (node (ref "S20") (pin "4") (pinfunction "G_4") (pintype "bidirectional"))
    )
    (net (code "30") (name "/SHIFTOUT20") (class "Default")
      (node (ref "IC3") (pin "4") (pinfunction "QE_4") (pintype "tri_state"))
      (node (ref "R24") (pin "2") (pinfunction "2_2") (pintype "passive"))
      (node (ref "S21") (pin "4") (pinfunction "G_4") (pintype "bidirectional"))
    )
    (net (code "31") (name "/SHIFTOUT21") (class "Default")
      (node (ref "IC3") (pin "5") (pinfunction "QF_5") (pintype "tri_state"))
      (node (ref "R25") (pin "2") (pinfunction "2_2") (pintype "passive"))
      (node (ref "S22") (pin "4") (pinfunction "G_4") (pintype "bidirectional"))
    )
    (net (code "32") (name "/SHIFTOUT22") (class "Default")
      (node (ref "IC3") (pin "6") (pinfunction "QG_6") (pintype "tri_state"))
      (node (ref "R26") (pin "2") (pinfunction "2_2") (pintype "passive"))
      (node (ref "S23") (pin "4") (pinfunction "G_4") (pintype "bidirectional"))
    )
    (net (code "33") (name "/SHIFTOUT23") (class "Default")
      (node (ref "IC3") (pin "7") (pinfunction "QH_7") (pintype "tri_state"))
      (node (ref "R27") (pin "2") (pinfunction "2_2") (pintype "passive"))
      (node (ref "S24") (pin "4") (pinfunction "G_4") (pintype "bidirectional"))
    )
    (net (code "34") (name "/SPISCK") (class "Default")
      (node (ref "ISP1") (pin "3") (pinfunction "SCK_3") (pintype "output"))
      (node (ref "U2") (pin "19") (pinfunction "PB5(SCK)_19") (pintype "bidirectional"))
    )
    (net (code "35") (name "5V") (class "Default")
      (node (ref "IC1") (pin "16") (pinfunction "VCC_16") (pintype "power_in"))
      (node (ref "IC2") (pin "16") (pinfunction "VCC_16") (pintype "power_in"))
      (node (ref "IC3") (pin "16") (pinfunction "VCC_16") (pintype "power_in"))
      (node (ref "IC5") (pin "2") (pinfunction "VO_2") (pintype "passive"))
      (node (ref "ISP1") (pin "2") (pinfunction "VCC_2") (pintype "power_in"))
      (node (ref "MR2") (pin "1") (pinfunction "1_1") (pintype "passive"))
      (node (ref "OK1") (pin "8") (pinfunction "VCC_8") (pintype "passive"))
      (node (ref "P4") (pin "1") (pinfunction "1_1") (pintype "passive"))
      (node (ref "R2") (pin "1") (pinfunction "1_1") (pintype "passive"))
      (node (ref "R4") (pin "1") (pinfunction "1_1") (pintype "passive"))
      (node (ref "RSTPULLP") (pin "2") (pinfunction "2_2") (pintype "passive"))
      (node (ref "U2") (pin "20") (pinfunction "AVCC_20") (pintype "bidirectional"))
      (node (ref "U2") (pin "21") (pinfunction "AREF_21") (pintype "bidirectional"))
      (node (ref "U2") (pin "7") (pinfunction "VCC_7") (pintype "bidirectional"))
    )
    (net (code "36") (name "GND") (class "Default")
      (node (ref "BATTERY") (pin "1") (pinfunction "1_1") (pintype "passive"))
      (node (ref "EXTERNRST") (pin "2") (pinfunction "2_2") (pintype "passive"))
      (node (ref "IC1") (pin "13") (pinfunction "G_13") (pintype "input"))
      (node (ref "IC1") (pin "8") (pinfunction "GND_8") (pintype "power_in"))
      (node (ref "IC2") (pin "13") (pinfunction "G_13") (pintype "input"))
      (node (ref "IC2") (pin "8") (pinfunction "GND_8") (pintype "power_in"))
      (node (ref "IC3") (pin "13") (pinfunction "G_13") (pintype "input"))
      (node (ref "IC3") (pin "8") (pinfunction "GND_8") (pintype "power_in"))
      (node (ref "IC4") (pin "3") (pinfunction "GND_3") (pintype "passive"))
      (node (ref "IC5") (pin "3") (pinfunction "GND_3") (pintype "passive"))
      (node (ref "ISP1") (pin "6") (pinfunction "GND_6") (pintype "power_in"))
      (node (ref "MIDI1") (pin "C") (pinfunction "C_C") (pintype "passive"))
      (node (ref "MIDI_D1") (pin "A") (pinfunction "A_A") (pintype "passive"))
      (node (ref "OK1") (pin "5") (pinfunction "GND_5") (pintype "passive"))
      (node (ref "P1") (pin "2") (pinfunction "2_2") (pintype "passive"))
      (node (ref "P2") (pin "2") (pinfunction "2_2") (pintype "passive"))
      (node (ref "P3") (pin "2") (pinfunction "2_2") (pintype "passive"))
      (node (ref "P4") (pin "2") (pinfunction "2_2") (pintype "passive"))
      (node (ref "P5") (pin "2") (pinfunction "2_2") (pintype "passive"))
      (node (ref "P6") (pin "2") (pinfunction "2_2") (pintype "passive"))
      (node (ref "POWER") (pin "C") (pinfunction "C_C") (pintype "passive"))
      (node (ref "RST") (pin "1") (pinfunction "1_1") (pintype "passive"))
      (node (ref "RST") (pin "2") (pinfunction "2_2") (pintype "passive"))
      (node (ref "S1") (pin "1") (pinfunction "S_1") (pintype "bidirectional"))
      (node (ref "S1") (pin "2") (pinfunction "S_2") (pintype "bidirectional"))
      (node (ref "S1") (pin "3") (pinfunction "S_3") (pintype "bidirectional"))
      (node (ref "S10") (pin "1") (pinfunction "S_1") (pintype "bidirectional"))
      (node (ref "S10") (pin "2") (pinfunction "S_2") (pintype "bidirectional"))
      (node (ref "S10") (pin "3") (pinfunction "S_3") (pintype "bidirectional"))
      (node (ref "S11") (pin "1") (pinfunction "S_1") (pintype "bidirectional"))
      (node (ref "S11") (pin "2") (pinfunction "S_2") (pintype "bidirectional"))
      (node (ref "S11") (pin "3") (pinfunction "S_3") (pintype "bidirectional"))
      (node (ref "S12") (pin "1") (pinfunction "S_1") (pintype "bidirectional"))
      (node (ref "S12") (pin "2") (pinfunction "S_2") (pintype "bidirectional"))
      (node (ref "S12") (pin "3") (pinfunction "S_3") (pintype "bidirectional"))
      (node (ref "S13") (pin "1") (pinfunction "S_1") (pintype "bidirectional"))
      (node (ref "S13") (pin "2") (pinfunction "S_2") (pintype "bidirectional"))
      (node (ref "S13") (pin "3") (pinfunction "S_3") (pintype "bidirectional"))
      (node (ref "S14") (pin "1") (pinfunction "S_1") (pintype "bidirectional"))
      (node (ref "S14") (pin "2") (pinfunction "S_2") (pintype "bidirectional"))
      (node (ref "S14") (pin "3") (pinfunction "S_3") (pintype "bidirectional"))
      (node (ref "S15") (pin "1") (pinfunction "S_1") (pintype "bidirectional"))
      (node (ref "S15") (pin "2") (pinfunction "S_2") (pintype "bidirectional"))
      (node (ref "S15") (pin "3") (pinfunction "S_3") (pintype "bidirectional"))
      (node (ref "S16") (pin "1") (pinfunction "S_1") (pintype "bidirectional"))
      (node (ref "S16") (pin "2") (pinfunction "S_2") (pintype "bidirectional"))
      (node (ref "S16") (pin "3") (pinfunction "S_3") (pintype "bidirectional"))
      (node (ref "S17") (pin "1") (pinfunction "S_1") (pintype "bidirectional"))
      (node (ref "S17") (pin "2") (pinfunction "S_2") (pintype "bidirectional"))
      (node (ref "S17") (pin "3") (pinfunction "S_3") (pintype "bidirectional"))
      (node (ref "S18") (pin "1") (pinfunction "S_1") (pintype "bidirectional"))
      (node (ref "S18") (pin "2") (pinfunction "S_2") (pintype "bidirectional"))
      (node (ref "S18") (pin "3") (pinfunction "S_3") (pintype "bidirectional"))
      (node (ref "S19") (pin "1") (pinfunction "S_1") (pintype "bidirectional"))
      (node (ref "S19") (pin "2") (pinfunction "S_2") (pintype "bidirectional"))
      (node (ref "S19") (pin "3") (pinfunction "S_3") (pintype "bidirectional"))
      (node (ref "S2") (pin "1") (pinfunction "S_1") (pintype "bidirectional"))
      (node (ref "S2") (pin "2") (pinfunction "S_2") (pintype "bidirectional"))
      (node (ref "S2") (pin "3") (pinfunction "S_3") (pintype "bidirectional"))
      (node (ref "S20") (pin "1") (pinfunction "S_1") (pintype "bidirectional"))
      (node (ref "S20") (pin "2") (pinfunction "S_2") (pintype "bidirectional"))
      (node (ref "S20") (pin "3") (pinfunction "S_3") (pintype "bidirectional"))
      (node (ref "S21") (pin "1") (pinfunction "S_1") (pintype "bidirectional"))
      (node (ref "S21") (pin "2") (pinfunction "S_2") (pintype "bidirectional"))
      (node (ref "S21") (pin "3") (pinfunction "S_3") (pintype "bidirectional"))
      (node (ref "S22") (pin "1") (pinfunction "S_1") (pintype "bidirectional"))
      (node (ref "S22") (pin "2") (pinfunction "S_2") (pintype "bidirectional"))
      (node (ref "S22") (pin "3") (pinfunction "S_3") (pintype "bidirectional"))
      (node (ref "S23") (pin "1") (pinfunction "S_1") (pintype "bidirectional"))
      (node (ref "S23") (pin "2") (pinfunction "S_2") (pintype "bidirectional"))
      (node (ref "S23") (pin "3") (pinfunction "S_3") (pintype "bidirectional"))
      (node (ref "S24") (pin "1") (pinfunction "S_1") (pintype "bidirectional"))
      (node (ref "S24") (pin "2") (pinfunction "S_2") (pintype "bidirectional"))
      (node (ref "S24") (pin "3") (pinfunction "S_3") (pintype "bidirectional"))
      (node (ref "S3") (pin "1") (pinfunction "S_1") (pintype "bidirectional"))
      (node (ref "S3") (pin "2") (pinfunction "S_2") (pintype "bidirectional"))
      (node (ref "S3") (pin "3") (pinfunction "S_3") (pintype "bidirectional"))
      (node (ref "S4") (pin "1") (pinfunction "S_1") (pintype "bidirectional"))
      (node (ref "S4") (pin "2") (pinfunction "S_2") (pintype "bidirectional"))
      (node (ref "S4") (pin "3") (pinfunction "S_3") (pintype "bidirectional"))
      (node (ref "S5") (pin "1") (pinfunction "S_1") (pintype "bidirectional"))
      (node (ref "S5") (pin "2") (pinfunction "S_2") (pintype "bidirectional"))
      (node (ref "S5") (pin "3") (pinfunction "S_3") (pintype "bidirectional"))
      (node (ref "S6") (pin "1") (pinfunction "S_1") (pintype "bidirectional"))
      (node (ref "S6") (pin "2") (pinfunction "S_2") (pintype "bidirectional"))
      (node (ref "S6") (pin "3") (pinfunction "S_3") (pintype "bidirectional"))
      (node (ref "S7") (pin "1") (pinfunction "S_1") (pintype "bidirectional"))
      (node (ref "S7") (pin "2") (pinfunction "S_2") (pintype "bidirectional"))
      (node (ref "S7") (pin "3") (pinfunction "S_3") (pintype "bidirectional"))
      (node (ref "S8") (pin "1") (pinfunction "S_1") (pintype "bidirectional"))
      (node (ref "S8") (pin "2") (pinfunction "S_2") (pintype "bidirectional"))
      (node (ref "S8") (pin "3") (pinfunction "S_3") (pintype "bidirectional"))
      (node (ref "S9") (pin "1") (pinfunction "S_1") (pintype "bidirectional"))
      (node (ref "S9") (pin "2") (pinfunction "S_2") (pintype "bidirectional"))
      (node (ref "S9") (pin "3") (pinfunction "S_3") (pintype "bidirectional"))
      (node (ref "SOL1") (pin "C") (pinfunction "C_C") (pintype "passive"))
      (node (ref "SOL10") (pin "C") (pinfunction "C_C") (pintype "passive"))
      (node (ref "SOL11") (pin "C") (pinfunction "C_C") (pintype "passive"))
      (node (ref "SOL12") (pin "C") (pinfunction "C_C") (pintype "passive"))
      (node (ref "SOL13") (pin "C") (pinfunction "C_C") (pintype "passive"))
      (node (ref "SOL14") (pin "C") (pinfunction "C_C") (pintype "passive"))
      (node (ref "SOL15") (pin "C") (pinfunction "C_C") (pintype "passive"))
      (node (ref "SOL16") (pin "C") (pinfunction "C_C") (pintype "passive"))
      (node (ref "SOL17") (pin "C") (pinfunction "C_C") (pintype "passive"))
      (node (ref "SOL18") (pin "C") (pinfunction "C_C") (pintype "passive"))
      (node (ref "SOL19") (pin "C") (pinfunction "C_C") (pintype "passive"))
      (node (ref "SOL2") (pin "C") (pinfunction "C_C") (pintype "passive"))
      (node (ref "SOL20") (pin "C") (pinfunction "C_C") (pintype "passive"))
      (node (ref "SOL21") (pin "C") (pinfunction "C_C") (pintype "passive"))
      (node (ref "SOL22") (pin "C") (pinfunction "C_C") (pintype "passive"))
      (node (ref "SOL23") (pin "C") (pinfunction "C_C") (pintype "passive"))
      (node (ref "SOL24") (pin "C") (pinfunction "C_C") (pintype "passive"))
      (node (ref "SOL3") (pin "C") (pinfunction "C_C") (pintype "passive"))
      (node (ref "SOL4") (pin "C") (pinfunction "C_C") (pintype "passive"))
      (node (ref "SOL5") (pin "C") (pinfunction "C_C") (pintype "passive"))
      (node (ref "SOL6") (pin "C") (pinfunction "C_C") (pintype "passive"))
      (node (ref "SOL7") (pin "C") (pinfunction "C_C") (pintype "passive"))
      (node (ref "SOL8") (pin "C") (pinfunction "C_C") (pintype "passive"))
      (node (ref "SOL9") (pin "C") (pinfunction "C_C") (pintype "passive"))
      (node (ref "U2") (pin "22") (pinfunction "GND_22") (pintype "bidirectional"))
      (node (ref "U2") (pin "8") (pinfunction "GND_8") (pintype "bidirectional"))
    )
    (net (code "37") (name "Net-(IC1-QH*)") (class "Default")
      (node (ref "IC1") (pin "9") (pinfunction "QH*_9") (pintype "tri_state"))
      (node (ref "IC3") (pin "14") (pinfunction "SER_14") (pintype "input"))
    )
    (net (code "38") (name "Net-(IC1-SER)") (class "Default")
      (node (ref "IC1") (pin "14") (pinfunction "SER_14") (pintype "input"))
      (node (ref "IC2") (pin "9") (pinfunction "QH*_9") (pintype "tri_state"))
    )
    (net (code "39") (name "Net-(MIDI-PadA)") (class "Default")
      (node (ref "MIDI") (pin "A") (pinfunction "A_A") (pintype "passive"))
      (node (ref "R4") (pin "2") (pinfunction "2_2") (pintype "passive"))
    )
    (net (code "40") (name "Net-(MIDI1-PadA)") (class "Default")
      (node (ref "MIDI1") (pin "A") (pinfunction "A_A") (pintype "passive"))
      (node (ref "R1") (pin "1") (pinfunction "1_1") (pintype "passive"))
    )
    (net (code "41") (name "Net-(OK1-A)") (class "Default")
      (node (ref "MIDI_D") (pin "C") (pinfunction "C_C") (pintype "passive"))
      (node (ref "MR1") (pin "1") (pinfunction "1_1") (pintype "passive"))
      (node (ref "OK1") (pin "2") (pinfunction "A_2") (pintype "passive"))
    )
    (net (code "42") (name "Net-(OK1-C)") (class "Default")
      (node (ref "MIDI_D") (pin "A") (pinfunction "A_A") (pintype "passive"))
      (node (ref "OK1") (pin "3") (pinfunction "C_3") (pintype "passive"))
      (node (ref "U$3") (pin "4") (pinfunction "MIDI_IN_4") (pintype "bidirectional"))
    )
    (net (code "43") (name "Net-(POWER-PadA)") (class "Default")
      (node (ref "POWER") (pin "A") (pinfunction "A_A") (pintype "passive"))
      (node (ref "R2") (pin "2") (pinfunction "2_2") (pintype "passive"))
    )
    (net (code "44") (name "Net-(R3-Pad1)") (class "Default")
      (node (ref "R3") (pin "1") (pinfunction "1_1") (pintype "passive"))
      (node (ref "SOL1") (pin "A") (pinfunction "A_A") (pintype "passive"))
    )
    (net (code "45") (name "Net-(R5-Pad1)") (class "Default")
      (node (ref "R5") (pin "1") (pinfunction "1_1") (pintype "passive"))
      (node (ref "SOL2") (pin "A") (pinfunction "A_A") (pintype "passive"))
    )
    (net (code "46") (name "Net-(R6-Pad1)") (class "Default")
      (node (ref "R6") (pin "1") (pinfunction "1_1") (pintype "passive"))
      (node (ref "SOL3") (pin "A") (pinfunction "A_A") (pintype "passive"))
    )
    (net (code "47") (name "Net-(R7-Pad1)") (class "Default")
      (node (ref "R7") (pin "1") (pinfunction "1_1") (pintype "passive"))
      (node (ref "SOL4") (pin "A") (pinfunction "A_A") (pintype "passive"))
    )
    (net (code "48") (name "Net-(R8-Pad1)") (class "Default")
      (node (ref "R8") (pin "1") (pinfunction "1_1") (pintype "passive"))
      (node (ref "SOL5") (pin "A") (pinfunction "A_A") (pintype "passive"))
    )
    (net (code "49") (name "Net-(R9-Pad1)") (class "Default")
      (node (ref "R9") (pin "1") (pinfunction "1_1") (pintype "passive"))
      (node (ref "SOL6") (pin "A") (pinfunction "A_A") (pintype "passive"))
    )
    (net (code "50") (name "Net-(R10-Pad1)") (class "Default")
      (node (ref "R10") (pin "1") (pinfunction "1_1") (pintype "passive"))
      (node (ref "SOL7") (pin "A") (pinfunction "A_A") (pintype "passive"))
    )
    (net (code "51") (name "Net-(R11-Pad1)") (class "Default")
      (node (ref "R11") (pin "1") (pinfunction "1_1") (pintype "passive"))
      (node (ref "SOL8") (pin "A") (pinfunction "A_A") (pintype "passive"))
    )
    (net (code "52") (name "Net-(R12-Pad1)") (class "Default")
      (node (ref "R12") (pin "1") (pinfunction "1_1") (pintype "passive"))
      (node (ref "SOL9") (pin "A") (pinfunction "A_A") (pintype "passive"))
    )
    (net (code "53") (name "Net-(R13-Pad1)") (class "Default")
      (node (ref "R13") (pin "1") (pinfunction "1_1") (pintype "passive"))
      (node (ref "SOL10") (pin "A") (pinfunction "A_A") (pintype "passive"))
    )
    (net (code "54") (name "Net-(R14-Pad1)") (class "Default")
      (node (ref "R14") (pin "1") (pinfunction "1_1") (pintype "passive"))
      (node (ref "SOL11") (pin "A") (pinfunction "A_A") (pintype "passive"))
    )
    (net (code "55") (name "Net-(R15-Pad1)") (class "Default")
      (node (ref "R15") (pin "1") (pinfunction "1_1") (pintype "passive"))
      (node (ref "SOL12") (pin "A") (pinfunction "A_A") (pintype "passive"))
    )
    (net (code "56") (name "Net-(R16-Pad1)") (class "Default")
      (node (ref "R16") (pin "1") (pinfunction "1_1") (pintype "passive"))
      (node (ref "SOL13") (pin "A") (pinfunction "A_A") (pintype "passive"))
    )
    (net (code "57") (name "Net-(R17-Pad1)") (class "Default")
      (node (ref "R17") (pin "1") (pinfunction "1_1") (pintype "passive"))
      (node (ref "SOL14") (pin "A") (pinfunction "A_A") (pintype "passive"))
    )
    (net (code "58") (name "Net-(R18-Pad1)") (class "Default")
      (node (ref "R18") (pin "1") (pinfunction "1_1") (pintype "passive"))
      (node (ref "SOL15") (pin "A") (pinfunction "A_A") (pintype "passive"))
    )
    (net (code "59") (name "Net-(R19-Pad1)") (class "Default")
      (node (ref "R19") (pin "1") (pinfunction "1_1") (pintype "passive"))
      (node (ref "SOL16") (pin "A") (pinfunction "A_A") (pintype "passive"))
    )
    (net (code "60") (name "Net-(R20-Pad1)") (class "Default")
      (node (ref "R20") (pin "1") (pinfunction "1_1") (pintype "passive"))
      (node (ref "SOL17") (pin "A") (pinfunction "A_A") (pintype "passive"))
    )
    (net (code "61") (name "Net-(R21-Pad1)") (class "Default")
      (node (ref "R21") (pin "1") (pinfunction "1_1") (pintype "passive"))
      (node (ref "SOL18") (pin "A") (pinfunction "A_A") (pintype "passive"))
    )
    (net (code "62") (name "Net-(R22-Pad1)") (class "Default")
      (node (ref "R22") (pin "1") (pinfunction "1_1") (pintype "passive"))
      (node (ref "SOL19") (pin "A") (pinfunction "A_A") (pintype "passive"))
    )
    (net (code "63") (name "Net-(R23-Pad1)") (class "Default")
      (node (ref "R23") (pin "1") (pinfunction "1_1") (pintype "passive"))
      (node (ref "SOL20") (pin "A") (pinfunction "A_A") (pintype "passive"))
    )
    (net (code "64") (name "Net-(R24-Pad1)") (class "Default")
      (node (ref "R24") (pin "1") (pinfunction "1_1") (pintype "passive"))
      (node (ref "SOL21") (pin "A") (pinfunction "A_A") (pintype "passive"))
    )
    (net (code "65") (name "Net-(R25-Pad1)") (class "Default")
      (node (ref "R25") (pin "1") (pinfunction "1_1") (pintype "passive"))
      (node (ref "SOL22") (pin "A") (pinfunction "A_A") (pintype "passive"))
    )
    (net (code "66") (name "Net-(R26-Pad1)") (class "Default")
      (node (ref "R26") (pin "1") (pinfunction "1_1") (pintype "passive"))
      (node (ref "SOL23") (pin "A") (pinfunction "A_A") (pintype "passive"))
    )
    (net (code "67") (name "Net-(R27-Pad1)") (class "Default")
      (node (ref "R27") (pin "1") (pinfunction "1_1") (pintype "passive"))
      (node (ref "SOL24") (pin "A") (pinfunction "A_A") (pintype "passive"))
    )
    (net (code "68") (name "Net-(S1-D-Pad5)") (class "Default")
      (node (ref "S1") (pin "5") (pinfunction "D_5") (pintype "bidirectional"))
      (node (ref "S1") (pin "6") (pinfunction "D_6") (pintype "bidirectional"))
      (node (ref "S1") (pin "7") (pinfunction "D_7") (pintype "bidirectional"))
      (node (ref "S1") (pin "8") (pinfunction "D_8") (pintype "bidirectional"))
      (node (ref "SCAP1") (pin "2") (pinfunction "2_2") (pintype "passive"))
      (node (ref "SCON1") (pin "2") (pinfunction "2_2") (pintype "passive"))
      (node (ref "SDI1") (pin "A") (pinfunction "A_A") (pintype "passive"))
    )
    (net (code "69") (name "Net-(S2-D-Pad5)") (class "Default")
      (node (ref "S2") (pin "5") (pinfunction "D_5") (pintype "bidirectional"))
      (node (ref "S2") (pin "6") (pinfunction "D_6") (pintype "bidirectional"))
      (node (ref "S2") (pin "7") (pinfunction "D_7") (pintype "bidirectional"))
      (node (ref "S2") (pin "8") (pinfunction "D_8") (pintype "bidirectional"))
      (node (ref "SCAP2") (pin "2") (pinfunction "2_2") (pintype "passive"))
      (node (ref "SCON2") (pin "2") (pinfunction "2_2") (pintype "passive"))
      (node (ref "SDI2") (pin "A") (pinfunction "A_A") (pintype "passive"))
    )
    (net (code "70") (name "Net-(S3-D-Pad5)") (class "Default")
      (node (ref "S3") (pin "5") (pinfunction "D_5") (pintype "bidirectional"))
      (node (ref "S3") (pin "6") (pinfunction "D_6") (pintype "bidirectional"))
      (node (ref "S3") (pin "7") (pinfunction "D_7") (pintype "bidirectional"))
      (node (ref "S3") (pin "8") (pinfunction "D_8") (pintype "bidirectional"))
      (node (ref "SCAP3") (pin "2") (pinfunction "2_2") (pintype "passive"))
      (node (ref "SCON3") (pin "2") (pinfunction "2_2") (pintype "passive"))
      (node (ref "SDI3") (pin "A") (pinfunction "A_A") (pintype "passive"))
    )
    (net (code "71") (name "Net-(S4-D-Pad5)") (class "Default")
      (node (ref "S4") (pin "5") (pinfunction "D_5") (pintype "bidirectional"))
      (node (ref "S4") (pin "6") (pinfunction "D_6") (pintype "bidirectional"))
      (node (ref "S4") (pin "7") (pinfunction "D_7") (pintype "bidirectional"))
      (node (ref "S4") (pin "8") (pinfunction "D_8") (pintype "bidirectional"))
      (node (ref "SCAP4") (pin "2") (pinfunction "2_2") (pintype "passive"))
      (node (ref "SCON4") (pin "2") (pinfunction "2_2") (pintype "passive"))
      (node (ref "SDI4") (pin "A") (pinfunction "A_A") (pintype "passive"))
    )
    (net (code "72") (name "Net-(S5-D-Pad5)") (class "Default")
      (node (ref "S5") (pin "5") (pinfunction "D_5") (pintype "bidirectional"))
      (node (ref "S5") (pin "6") (pinfunction "D_6") (pintype "bidirectional"))
      (node (ref "S5") (pin "7") (pinfunction "D_7") (pintype "bidirectional"))
      (node (ref "S5") (pin "8") (pinfunction "D_8") (pintype "bidirectional"))
      (node (ref "SCAP5") (pin "2") (pinfunction "2_2") (pintype "passive"))
      (node (ref "SCON5") (pin "2") (pinfunction "2_2") (pintype "passive"))
      (node (ref "SDI5") (pin "A") (pinfunction "A_A") (pintype "passive"))
    )
    (net (code "73") (name "Net-(S6-D-Pad5)") (class "Default")
      (node (ref "S6") (pin "5") (pinfunction "D_5") (pintype "bidirectional"))
      (node (ref "S6") (pin "6") (pinfunction "D_6") (pintype "bidirectional"))
      (node (ref "S6") (pin "7") (pinfunction "D_7") (pintype "bidirectional"))
      (node (ref "S6") (pin "8") (pinfunction "D_8") (pintype "bidirectional"))
      (node (ref "SCAP6") (pin "2") (pinfunction "2_2") (pintype "passive"))
      (node (ref "SCON6") (pin "2") (pinfunction "2_2") (pintype "passive"))
      (node (ref "SDI6") (pin "A") (pinfunction "A_A") (pintype "passive"))
    )
    (net (code "74") (name "Net-(S7-D-Pad5)") (class "Default")
      (node (ref "S7") (pin "5") (pinfunction "D_5") (pintype "bidirectional"))
      (node (ref "S7") (pin "6") (pinfunction "D_6") (pintype "bidirectional"))
      (node (ref "S7") (pin "7") (pinfunction "D_7") (pintype "bidirectional"))
      (node (ref "S7") (pin "8") (pinfunction "D_8") (pintype "bidirectional"))
      (node (ref "SCAP7") (pin "2") (pinfunction "2_2") (pintype "passive"))
      (node (ref "SCON7") (pin "2") (pinfunction "2_2") (pintype "passive"))
      (node (ref "SDI7") (pin "A") (pinfunction "A_A") (pintype "passive"))
    )
    (net (code "75") (name "Net-(S8-D-Pad5)") (class "Default")
      (node (ref "S8") (pin "5") (pinfunction "D_5") (pintype "bidirectional"))
      (node (ref "S8") (pin "6") (pinfunction "D_6") (pintype "bidirectional"))
      (node (ref "S8") (pin "7") (pinfunction "D_7") (pintype "bidirectional"))
      (node (ref "S8") (pin "8") (pinfunction "D_8") (pintype "bidirectional"))
      (node (ref "SCAP8") (pin "2") (pinfunction "2_2") (pintype "passive"))
      (node (ref "SCON8") (pin "2") (pinfunction "2_2") (pintype "passive"))
      (node (ref "SDI8") (pin "A") (pinfunction "A_A") (pintype "passive"))
    )
    (net (code "76") (name "Net-(S9-D-Pad5)") (class "Default")
      (node (ref "S9") (pin "5") (pinfunction "D_5") (pintype "bidirectional"))
      (node (ref "S9") (pin "6") (pinfunction "D_6") (pintype "bidirectional"))
      (node (ref "S9") (pin "7") (pinfunction "D_7") (pintype "bidirectional"))
      (node (ref "S9") (pin "8") (pinfunction "D_8") (pintype "bidirectional"))
      (node (ref "SCAP9") (pin "2") (pinfunction "2_2") (pintype "passive"))
      (node (ref "SCON9") (pin "2") (pinfunction "2_2") (pintype "passive"))
      (node (ref "SDI9") (pin "A") (pinfunction "A_A") (pintype "passive"))
    )
    (net (code "77") (name "Net-(S10-D-Pad5)") (class "Default")
      (node (ref "S10") (pin "5") (pinfunction "D_5") (pintype "bidirectional"))
      (node (ref "S10") (pin "6") (pinfunction "D_6") (pintype "bidirectional"))
      (node (ref "S10") (pin "7") (pinfunction "D_7") (pintype "bidirectional"))
      (node (ref "S10") (pin "8") (pinfunction "D_8") (pintype "bidirectional"))
      (node (ref "SCAP10") (pin "2") (pinfunction "2_2") (pintype "passive"))
      (node (ref "SCON10") (pin "2") (pinfunction "2_2") (pintype "passive"))
      (node (ref "SDI10") (pin "A") (pinfunction "A_A") (pintype "passive"))
    )
    (net (code "78") (name "Net-(S11-D-Pad5)") (class "Default")
      (node (ref "S11") (pin "5") (pinfunction "D_5") (pintype "bidirectional"))
      (node (ref "S11") (pin "6") (pinfunction "D_6") (pintype "bidirectional"))
      (node (ref "S11") (pin "7") (pinfunction "D_7") (pintype "bidirectional"))
      (node (ref "S11") (pin "8") (pinfunction "D_8") (pintype "bidirectional"))
      (node (ref "SCAP11") (pin "2") (pinfunction "2_2") (pintype "passive"))
      (node (ref "SCON11") (pin "2") (pinfunction "2_2") (pintype "passive"))
      (node (ref "SDI11") (pin "A") (pinfunction "A_A") (pintype "passive"))
    )
    (net (code "79") (name "Net-(S12-D-Pad5)") (class "Default")
      (node (ref "S12") (pin "5") (pinfunction "D_5") (pintype "bidirectional"))
      (node (ref "S12") (pin "6") (pinfunction "D_6") (pintype "bidirectional"))
      (node (ref "S12") (pin "7") (pinfunction "D_7") (pintype "bidirectional"))
      (node (ref "S12") (pin "8") (pinfunction "D_8") (pintype "bidirectional"))
      (node (ref "SCAP12") (pin "2") (pinfunction "2_2") (pintype "passive"))
      (node (ref "SCON12") (pin "2") (pinfunction "2_2") (pintype "passive"))
      (node (ref "SDI12") (pin "A") (pinfunction "A_A") (pintype "passive"))
    )
    (net (code "80") (name "Net-(S13-D-Pad5)") (class "Default")
      (node (ref "S13") (pin "5") (pinfunction "D_5") (pintype "bidirectional"))
      (node (ref "S13") (pin "6") (pinfunction "D_6") (pintype "bidirectional"))
      (node (ref "S13") (pin "7") (pinfunction "D_7") (pintype "bidirectional"))
      (node (ref "S13") (pin "8") (pinfunction "D_8") (pintype "bidirectional"))
      (node (ref "SCAP13") (pin "2") (pinfunction "2_2") (pintype "passive"))
      (node (ref "SCON13") (pin "2") (pinfunction "2_2") (pintype "passive"))
      (node (ref "SDI13") (pin "A") (pinfunction "A_A") (pintype "passive"))
    )
    (net (code "81") (name "Net-(S14-D-Pad5)") (class "Default")
      (node (ref "S14") (pin "5") (pinfunction "D_5") (pintype "bidirectional"))
      (node (ref "S14") (pin "6") (pinfunction "D_6") (pintype "bidirectional"))
      (node (ref "S14") (pin "7") (pinfunction "D_7") (pintype "bidirectional"))
      (node (ref "S14") (pin "8") (pinfunction "D_8") (pintype "bidirectional"))
      (node (ref "SCAP14") (pin "2") (pinfunction "2_2") (pintype "passive"))
      (node (ref "SCON14") (pin "2") (pinfunction "2_2") (pintype "passive"))
      (node (ref "SDI14") (pin "A") (pinfunction "A_A") (pintype "passive"))
    )
    (net (code "82") (name "Net-(S15-D-Pad5)") (class "Default")
      (node (ref "S15") (pin "5") (pinfunction "D_5") (pintype "bidirectional"))
      (node (ref "S15") (pin "6") (pinfunction "D_6") (pintype "bidirectional"))
      (node (ref "S15") (pin "7") (pinfunction "D_7") (pintype "bidirectional"))
      (node (ref "S15") (pin "8") (pinfunction "D_8") (pintype "bidirectional"))
      (node (ref "SCAP15") (pin "2") (pinfunction "2_2") (pintype "passive"))
      (node (ref "SCON15") (pin "2") (pinfunction "2_2") (pintype "passive"))
      (node (ref "SDI15") (pin "A") (pinfunction "A_A") (pintype "passive"))
    )
    (net (code "83") (name "Net-(S16-D-Pad5)") (class "Default")
      (node (ref "S16") (pin "5") (pinfunction "D_5") (pintype "bidirectional"))
      (node (ref "S16") (pin "6") (pinfunction "D_6") (pintype "bidirectional"))
      (node (ref "S16") (pin "7") (pinfunction "D_7") (pintype "bidirectional"))
      (node (ref "S16") (pin "8") (pinfunction "D_8") (pintype "bidirectional"))
      (node (ref "SCAP16") (pin "2") (pinfunction "2_2") (pintype "passive"))
      (node (ref "SCON16") (pin "2") (pinfunction "2_2") (pintype "passive"))
      (node (ref "SDI16") (pin "A") (pinfunction "A_A") (pintype "passive"))
    )
    (net (code "84") (name "Net-(S17-D-Pad5)") (class "Default")
      (node (ref "S17") (pin "5") (pinfunction "D_5") (pintype "bidirectional"))
      (node (ref "S17") (pin "6") (pinfunction "D_6") (pintype "bidirectional"))
      (node (ref "S17") (pin "7") (pinfunction "D_7") (pintype "bidirectional"))
      (node (ref "S17") (pin "8") (pinfunction "D_8") (pintype "bidirectional"))
      (node (ref "SCAP17") (pin "2") (pinfunction "2_2") (pintype "passive"))
      (node (ref "SCON17") (pin "2") (pinfunction "2_2") (pintype "passive"))
      (node (ref "SDI17") (pin "A") (pinfunction "A_A") (pintype "passive"))
    )
    (net (code "85") (name "Net-(S18-D-Pad5)") (class "Default")
      (node (ref "S18") (pin "5") (pinfunction "D_5") (pintype "bidirectional"))
      (node (ref "S18") (pin "6") (pinfunction "D_6") (pintype "bidirectional"))
      (node (ref "S18") (pin "7") (pinfunction "D_7") (pintype "bidirectional"))
      (node (ref "S18") (pin "8") (pinfunction "D_8") (pintype "bidirectional"))
      (node (ref "SCAP18") (pin "2") (pinfunction "2_2") (pintype "passive"))
      (node (ref "SCON18") (pin "2") (pinfunction "2_2") (pintype "passive"))
      (node (ref "SDI18") (pin "A") (pinfunction "A_A") (pintype "passive"))
    )
    (net (code "86") (name "Net-(S19-D-Pad5)") (class "Default")
      (node (ref "S19") (pin "5") (pinfunction "D_5") (pintype "bidirectional"))
      (node (ref "S19") (pin "6") (pinfunction "D_6") (pintype "bidirectional"))
      (node (ref "S19") (pin "7") (pinfunction "D_7") (pintype "bidirectional"))
      (node (ref "S19") (pin "8") (pinfunction "D_8") (pintype "bidirectional"))
      (node (ref "SCAP19") (pin "2") (pinfunction "2_2") (pintype "passive"))
      (node (ref "SCON19") (pin "2") (pinfunction "2_2") (pintype "passive"))
      (node (ref "SDI19") (pin "A") (pinfunction "A_A") (pintype "passive"))
    )
    (net (code "87") (name "Net-(S20-D-Pad5)") (class "Default")
      (node (ref "S20") (pin "5") (pinfunction "D_5") (pintype "bidirectional"))
      (node (ref "S20") (pin "6") (pinfunction "D_6") (pintype "bidirectional"))
      (node (ref "S20") (pin "7") (pinfunction "D_7") (pintype "bidirectional"))
      (node (ref "S20") (pin "8") (pinfunction "D_8") (pintype "bidirectional"))
      (node (ref "SCAP20") (pin "2") (pinfunction "2_2") (pintype "passive"))
      (node (ref "SCON20") (pin "2") (pinfunction "2_2") (pintype "passive"))
      (node (ref "SDI20") (pin "A") (pinfunction "A_A") (pintype "passive"))
    )
    (net (code "88") (name "Net-(S21-D-Pad5)") (class "Default")
      (node (ref "S21") (pin "5") (pinfunction "D_5") (pintype "bidirectional"))
      (node (ref "S21") (pin "6") (pinfunction "D_6") (pintype "bidirectional"))
      (node (ref "S21") (pin "7") (pinfunction "D_7") (pintype "bidirectional"))
      (node (ref "S21") (pin "8") (pinfunction "D_8") (pintype "bidirectional"))
      (node (ref "SCAP21") (pin "2") (pinfunction "2_2") (pintype "passive"))
      (node (ref "SCON21") (pin "2") (pinfunction "2_2") (pintype "passive"))
      (node (ref "SDI21") (pin "A") (pinfunction "A_A") (pintype "passive"))
    )
    (net (code "89") (name "Net-(S22-D-Pad5)") (class "Default")
      (node (ref "S22") (pin "5") (pinfunction "D_5") (pintype "bidirectional"))
      (node (ref "S22") (pin "6") (pinfunction "D_6") (pintype "bidirectional"))
      (node (ref "S22") (pin "7") (pinfunction "D_7") (pintype "bidirectional"))
      (node (ref "S22") (pin "8") (pinfunction "D_8") (pintype "bidirectional"))
      (node (ref "SCAP22") (pin "2") (pinfunction "2_2") (pintype "passive"))
      (node (ref "SCON22") (pin "2") (pinfunction "2_2") (pintype "passive"))
      (node (ref "SDI22") (pin "A") (pinfunction "A_A") (pintype "passive"))
    )
    (net (code "90") (name "Net-(S23-D-Pad5)") (class "Default")
      (node (ref "S23") (pin "5") (pinfunction "D_5") (pintype "bidirectional"))
      (node (ref "S23") (pin "6") (pinfunction "D_6") (pintype "bidirectional"))
      (node (ref "S23") (pin "7") (pinfunction "D_7") (pintype "bidirectional"))
      (node (ref "S23") (pin "8") (pinfunction "D_8") (pintype "bidirectional"))
      (node (ref "SCAP23") (pin "2") (pinfunction "2_2") (pintype "passive"))
      (node (ref "SCON23") (pin "2") (pinfunction "2_2") (pintype "passive"))
      (node (ref "SDI23") (pin "A") (pinfunction "A_A") (pintype "passive"))
    )
    (net (code "91") (name "Net-(S24-D-Pad5)") (class "Default")
      (node (ref "S24") (pin "5") (pinfunction "D_5") (pintype "bidirectional"))
      (node (ref "S24") (pin "6") (pinfunction "D_6") (pintype "bidirectional"))
      (node (ref "S24") (pin "7") (pinfunction "D_7") (pintype "bidirectional"))
      (node (ref "S24") (pin "8") (pinfunction "D_8") (pintype "bidirectional"))
      (node (ref "SCAP24") (pin "2") (pinfunction "2_2") (pintype "passive"))
      (node (ref "SCON24") (pin "2") (pinfunction "2_2") (pintype "passive"))
      (node (ref "SDI24") (pin "A") (pinfunction "A_A") (pintype "passive"))
    )
    (net (code "92") (name "Net-(U$3-MIDI_OUT)") (class "Default")
      (node (ref "MR1") (pin "2") (pinfunction "2_2") (pintype "passive"))
      (node (ref "U$3") (pin "5") (pinfunction "MIDI_OUT_5") (pintype "bidirectional"))
    )
    (net (code "93") (name "Net-(U2-PB6(XTAL1{slash}TOSC1))") (class "Default")
      (node (ref "P5") (pin "1") (pinfunction "1_1") (pintype "passive"))
      (node (ref "Q1") (pin "1") (pinfunction "1_1") (pintype "passive"))
      (node (ref "U2") (pin "9") (pinfunction "PB6(XTAL1/TOSC1)_9") (pintype "bidirectional"))
    )
    (net (code "94") (name "Net-(U2-PB7(XTAL2{slash}TOSC2))") (class "Default")
      (node (ref "P6") (pin "1") (pinfunction "1_1") (pintype "passive"))
      (node (ref "Q1") (pin "2") (pinfunction "2_2") (pintype "passive"))
      (node (ref "U2") (pin "10") (pinfunction "PB7(XTAL2/TOSC2)_10") (pintype "bidirectional"))
    )
    (net (code "95") (name "Net-(U2-PD6(AIN0))") (class "Default")
      (node (ref "JP1") (pin "1") (pinfunction "1_1") (pintype "passive"))
      (node (ref "U2") (pin "12") (pinfunction "PD6(AIN0)_12") (pintype "bidirectional"))
    )
    (net (code "96") (name "Net-(U2-PD7(AIN1))") (class "Default")
      (node (ref "JP1") (pin "2") (pinfunction "2_2") (pintype "passive"))
      (node (ref "U2") (pin "13") (pinfunction "PD7(AIN1)_13") (pintype "bidirectional"))
    )
    (net (code "97") (name "VCC") (class "Default")
      (node (ref "BATTERY") (pin "2") (pinfunction "2_2") (pintype "passive"))
      (node (ref "SWITCH") (pin "2") (pinfunction "2_2") (pintype "passive"))
    )
    (net (code "98") (name "VDD") (class "Default")
      (node (ref "IC4") (pin "1") (pinfunction "VI_1") (pintype "input"))
      (node (ref "MIDI_D1") (pin "C") (pinfunction "C_C") (pintype "passive"))
      (node (ref "P2") (pin "1") (pinfunction "1_1") (pintype "passive"))
      (node (ref "SCAP1") (pin "1") (pinfunction "1_1") (pintype "passive"))
      (node (ref "SCAP10") (pin "1") (pinfunction "1_1") (pintype "passive"))
      (node (ref "SCAP11") (pin "1") (pinfunction "1_1") (pintype "passive"))
      (node (ref "SCAP12") (pin "1") (pinfunction "1_1") (pintype "passive"))
      (node (ref "SCAP13") (pin "1") (pinfunction "1_1") (pintype "passive"))
      (node (ref "SCAP14") (pin "1") (pinfunction "1_1") (pintype "passive"))
      (node (ref "SCAP15") (pin "1") (pinfunction "1_1") (pintype "passive"))
      (node (ref "SCAP16") (pin "1") (pinfunction "1_1") (pintype "passive"))
      (node (ref "SCAP17") (pin "1") (pinfunction "1_1") (pintype "passive"))
      (node (ref "SCAP18") (pin "1") (pinfunction "1_1") (pintype "passive"))
      (node (ref "SCAP19") (pin "1") (pinfunction "1_1") (pintype "passive"))
      (node (ref "SCAP2") (pin "1") (pinfunction "1_1") (pintype "passive"))
      (node (ref "SCAP20") (pin "1") (pinfunction "1_1") (pintype "passive"))
      (node (ref "SCAP21") (pin "1") (pinfunction "1_1") (pintype "passive"))
      (node (ref "SCAP22") (pin "1") (pinfunction "1_1") (pintype "passive"))
      (node (ref "SCAP23") (pin "1") (pinfunction "1_1") (pintype "passive"))
      (node (ref "SCAP24") (pin "1") (pinfunction "1_1") (pintype "passive"))
      (node (ref "SCAP3") (pin "1") (pinfunction "1_1") (pintype "passive"))
      (node (ref "SCAP4") (pin "1") (pinfunction "1_1") (pintype "passive"))
      (node (ref "SCAP5") (pin "1") (pinfunction "1_1") (pintype "passive"))
      (node (ref "SCAP6") (pin "1") (pinfunction "1_1") (pintype "passive"))
      (node (ref "SCAP7") (pin "1") (pinfunction "1_1") (pintype "passive"))
      (node (ref "SCAP8") (pin "1") (pinfunction "1_1") (pintype "passive"))
      (node (ref "SCAP9") (pin "1") (pinfunction "1_1") (pintype "passive"))
      (node (ref "SCON1") (pin "1") (pinfunction "1_1") (pintype "passive"))
      (node (ref "SCON10") (pin "1") (pinfunction "1_1") (pintype "passive"))
      (node (ref "SCON11") (pin "1") (pinfunction "1_1") (pintype "passive"))
      (node (ref "SCON12") (pin "1") (pinfunction "1_1") (pintype "passive"))
      (node (ref "SCON13") (pin "1") (pinfunction "1_1") (pintype "passive"))
      (node (ref "SCON14") (pin "1") (pinfunction "1_1") (pintype "passive"))
      (node (ref "SCON15") (pin "1") (pinfunction "1_1") (pintype "passive"))
      (node (ref "SCON16") (pin "1") (pinfunction "1_1") (pintype "passive"))
      (node (ref "SCON17") (pin "1") (pinfunction "1_1") (pintype "passive"))
      (node (ref "SCON18") (pin "1") (pinfunction "1_1") (pintype "passive"))
      (node (ref "SCON19") (pin "1") (pinfunction "1_1") (pintype "passive"))
      (node (ref "SCON2") (pin "1") (pinfunction "1_1") (pintype "passive"))
      (node (ref "SCON20") (pin "1") (pinfunction "1_1") (pintype "passive"))
      (node (ref "SCON21") (pin "1") (pinfunction "1_1") (pintype "passive"))
      (node (ref "SCON22") (pin "1") (pinfunction "1_1") (pintype "passive"))
      (node (ref "SCON23") (pin "1") (pinfunction "1_1") (pintype "passive"))
      (node (ref "SCON24") (pin "1") (pinfunction "1_1") (pintype "passive"))
      (node (ref "SCON3") (pin "1") (pinfunction "1_1") (pintype "passive"))
      (node (ref "SCON4") (pin "1") (pinfunction "1_1") (pintype "passive"))
      (node (ref "SCON5") (pin "1") (pinfunction "1_1") (pintype "passive"))
      (node (ref "SCON6") (pin "1") (pinfunction "1_1") (pintype "passive"))
      (node (ref "SCON7") (pin "1") (pinfunction "1_1") (pintype "passive"))
      (node (ref "SCON8") (pin "1") (pinfunction "1_1") (pintype "passive"))
      (node (ref "SCON9") (pin "1") (pinfunction "1_1") (pintype "passive"))
      (node (ref "SDI1") (pin "C") (pinfunction "C_C") (pintype "passive"))
      (node (ref "SDI10") (pin "C") (pinfunction "C_C") (pintype "passive"))
      (node (ref "SDI11") (pin "C") (pinfunction "C_C") (pintype "passive"))
      (node (ref "SDI12") (pin "C") (pinfunction "C_C") (pintype "passive"))
      (node (ref "SDI13") (pin "C") (pinfunction "C_C") (pintype "passive"))
      (node (ref "SDI14") (pin "C") (pinfunction "C_C") (pintype "passive"))
      (node (ref "SDI15") (pin "C") (pinfunction "C_C") (pintype "passive"))
      (node (ref "SDI16") (pin "C") (pinfunction "C_C") (pintype "passive"))
      (node (ref "SDI17") (pin "C") (pinfunction "C_C") (pintype "passive"))
      (node (ref "SDI18") (pin "C") (pinfunction "C_C") (pintype "passive"))
      (node (ref "SDI19") (pin "C") (pinfunction "C_C") (pintype "passive"))
      (node (ref "SDI2") (pin "C") (pinfunction "C_C") (pintype "passive"))
      (node (ref "SDI20") (pin "C") (pinfunction "C_C") (pintype "passive"))
      (node (ref "SDI21") (pin "C") (pinfunction "C_C") (pintype "passive"))
      (node (ref "SDI22") (pin "C") (pinfunction "C_C") (pintype "passive"))
      (node (ref "SDI23") (pin "C") (pinfunction "C_C") (pintype "passive"))
      (node (ref "SDI24") (pin "C") (pinfunction "C_C") (pintype "passive"))
      (node (ref "SDI3") (pin "C") (pinfunction "C_C") (pintype "passive"))
      (node (ref "SDI4") (pin "C") (pinfunction "C_C") (pintype "passive"))
      (node (ref "SDI5") (pin "C") (pinfunction "C_C") (pintype "passive"))
      (node (ref "SDI6") (pin "C") (pinfunction "C_C") (pintype "passive"))
      (node (ref "SDI7") (pin "C") (pinfunction "C_C") (pintype "passive"))
      (node (ref "SDI8") (pin "C") (pinfunction "C_C") (pintype "passive"))
      (node (ref "SDI9") (pin "C") (pinfunction "C_C") (pintype "passive"))
      (node (ref "SWITCH") (pin "1") (pinfunction "1_1") (pintype "passive"))
    )
    (net (code "99") (name "unconnected-(IC1-SCL-Pad10)") (class "Default")
      (node (ref "IC1") (pin "10") (pinfunction "SCL_10") (pintype "input"))
    )
    (net (code "100") (name "unconnected-(IC2-SCL-Pad10)") (class "Default")
      (node (ref "IC2") (pin "10") (pinfunction "SCL_10") (pintype "input"))
    )
    (net (code "101") (name "unconnected-(IC3-QH*-Pad9)") (class "Default")
      (node (ref "IC3") (pin "9") (pinfunction "QH*_9") (pintype "tri_state"))
    )
    (net (code "102") (name "unconnected-(IC3-SCL-Pad10)") (class "Default")
      (node (ref "IC3") (pin "10") (pinfunction "SCL_10") (pintype "input"))
    )
    (net (code "103") (name "unconnected-(OK1-VB-Pad7)") (class "Default")
      (node (ref "OK1") (pin "7") (pinfunction "VB_7") (pintype "passive"))
    )
    (net (code "104") (name "unconnected-(U$3-NC1-Pad1)") (class "Default")
      (node (ref "U$3") (pin "1") (pinfunction "NC1_1") (pintype "bidirectional"))
    )
    (net (code "105") (name "unconnected-(U$3-NC2-Pad2)") (class "Default")
      (node (ref "U$3") (pin "2") (pinfunction "NC2_2") (pintype "bidirectional"))
    )
    (net (code "106") (name "unconnected-(U$3-NC3-Pad3)") (class "Default")
      (node (ref "U$3") (pin "3") (pinfunction "NC3_3") (pintype "bidirectional"))
    )
    (net (code "107") (name "unconnected-(U2-PB0(ICP)-Pad14)") (class "Default")
      (node (ref "U2") (pin "14") (pinfunction "PB0(ICP)_14") (pintype "bidirectional"))
    )
    (net (code "108") (name "unconnected-(U2-PB1(OC1A)-Pad15)") (class "Default")
      (node (ref "U2") (pin "15") (pinfunction "PB1(OC1A)_15") (pintype "bidirectional"))
    )
    (net (code "109") (name "unconnected-(U2-PB2(SS{slash}OC1B)-Pad16)") (class "Default")
      (node (ref "U2") (pin "16") (pinfunction "PB2(SS/OC1B)_16") (pintype "bidirectional"))
    )
    (net (code "110") (name "unconnected-(U2-PC1(ADC1)-Pad24)") (class "Default")
      (node (ref "U2") (pin "24") (pinfunction "PC1(ADC1)_24") (pintype "bidirectional"))
    )
    (net (code "111") (name "unconnected-(U2-PC2(ADC2)-Pad25)") (class "Default")
      (node (ref "U2") (pin "25") (pinfunction "PC2(ADC2)_25") (pintype "bidirectional"))
    )
    (net (code "112") (name "unconnected-(U2-PC3(ADC3)-Pad26)") (class "Default")
      (node (ref "U2") (pin "26") (pinfunction "PC3(ADC3)_26") (pintype "bidirectional"))
    )
    (net (code "113") (name "unconnected-(U2-PC4(ADC4{slash}SDA)-Pad27)") (class "Default")
      (node (ref "U2") (pin "27") (pinfunction "PC4(ADC4/SDA)_27") (pintype "bidirectional"))
    )
    (net (code "114") (name "unconnected-(U2-PC5(ADC5{slash}SCL)-Pad28)") (class "Default")
      (node (ref "U2") (pin "28") (pinfunction "PC5(ADC5/SCL)_28") (pintype "bidirectional"))
    )
    (net (code "115") (name "unconnected-(U2-PD1(TXD)-Pad3)") (class "Default")
      (node (ref "U2") (pin "3") (pinfunction "PD1(TXD)_3") (pintype "bidirectional"))
    )
    (net (code "116") (name "unconnected-(U2-PD5(T1)-Pad11)") (class "Default")
      (node (ref "U2") (pin "11") (pinfunction "PD5(T1)_11") (pintype "bidirectional"))
    )
  )
)
